# Fuel_Cell_Controller_V2.net
KiCad netlist of a schematic drawn in EAGLE
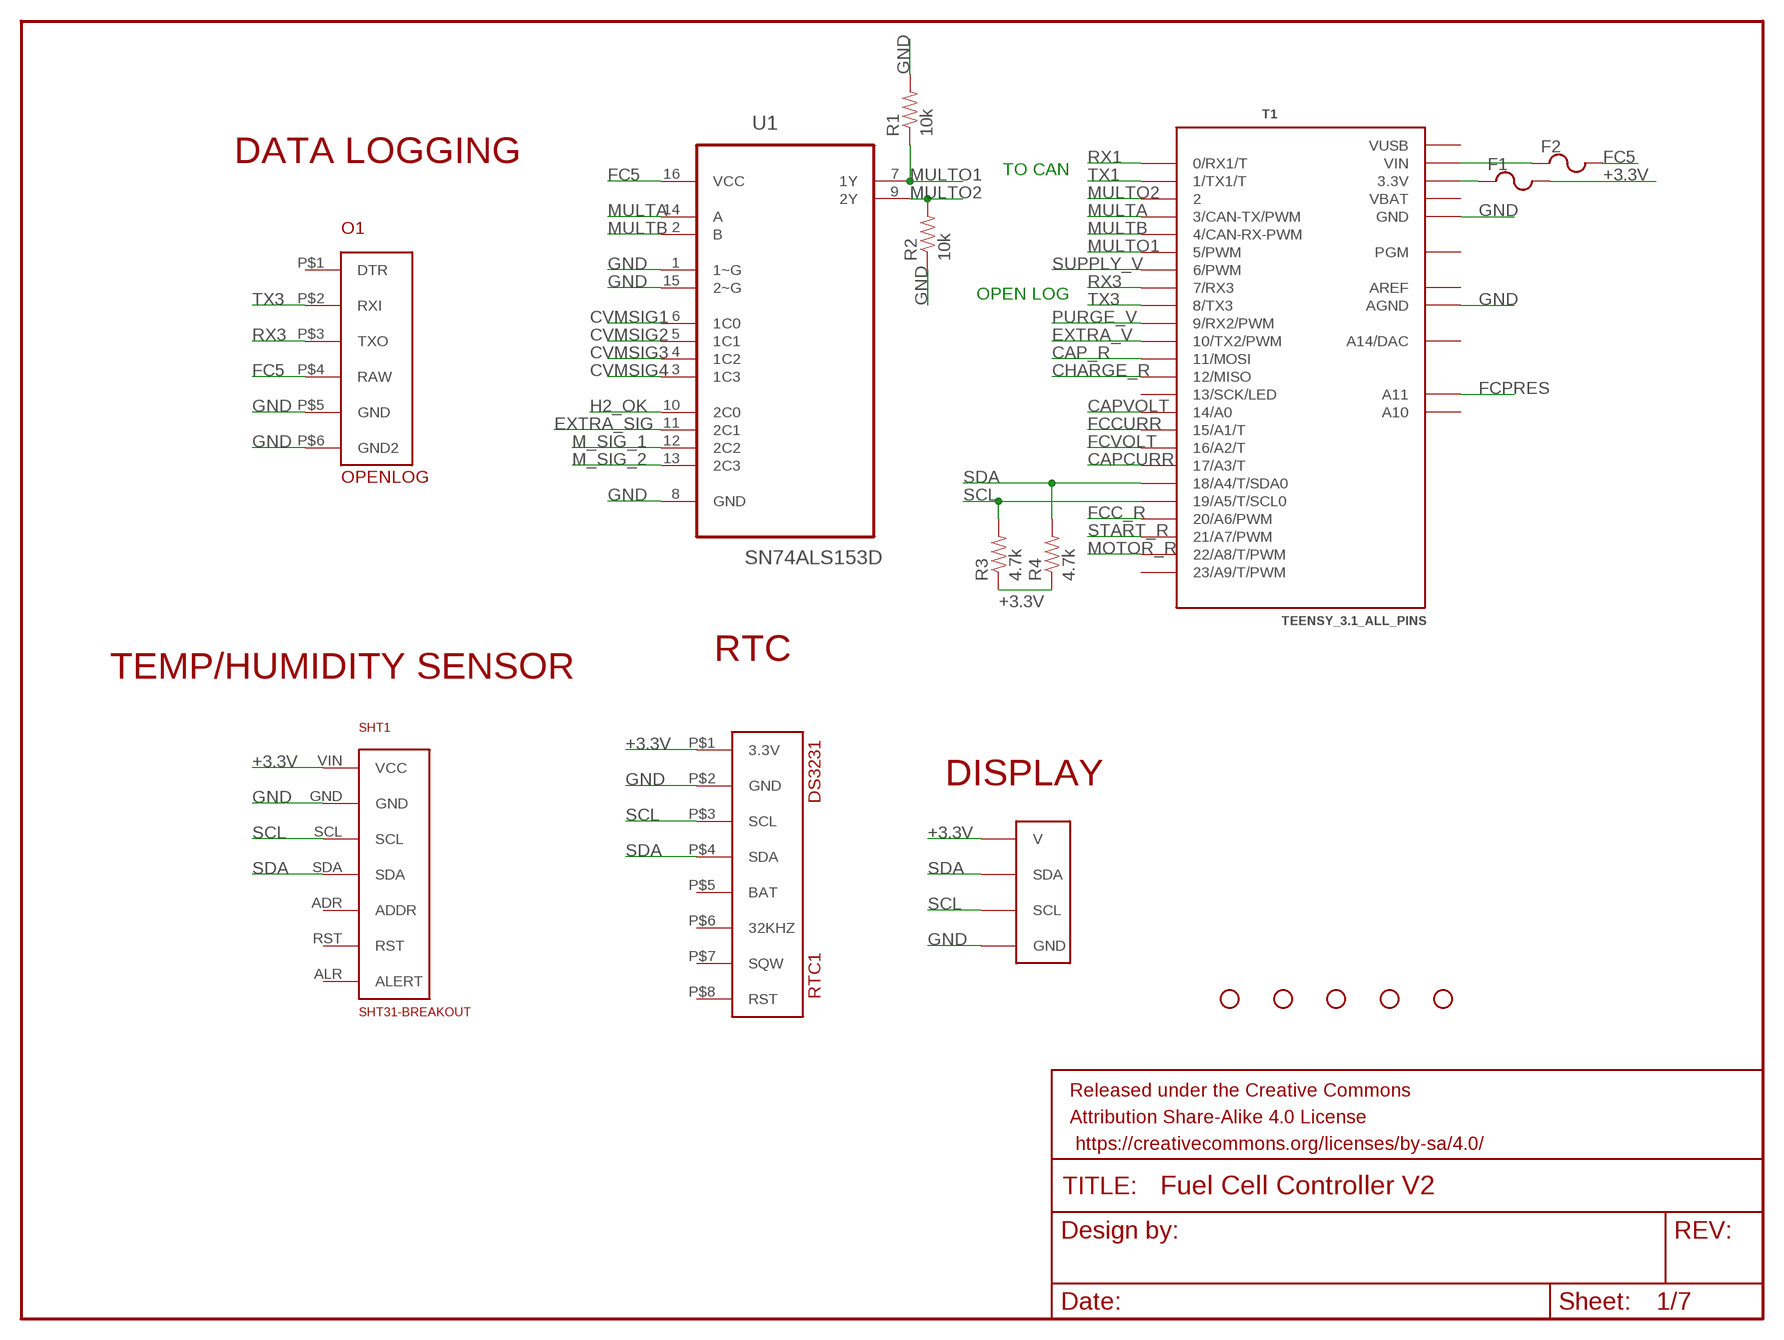
[diagram p0: schematic, sheet 1]
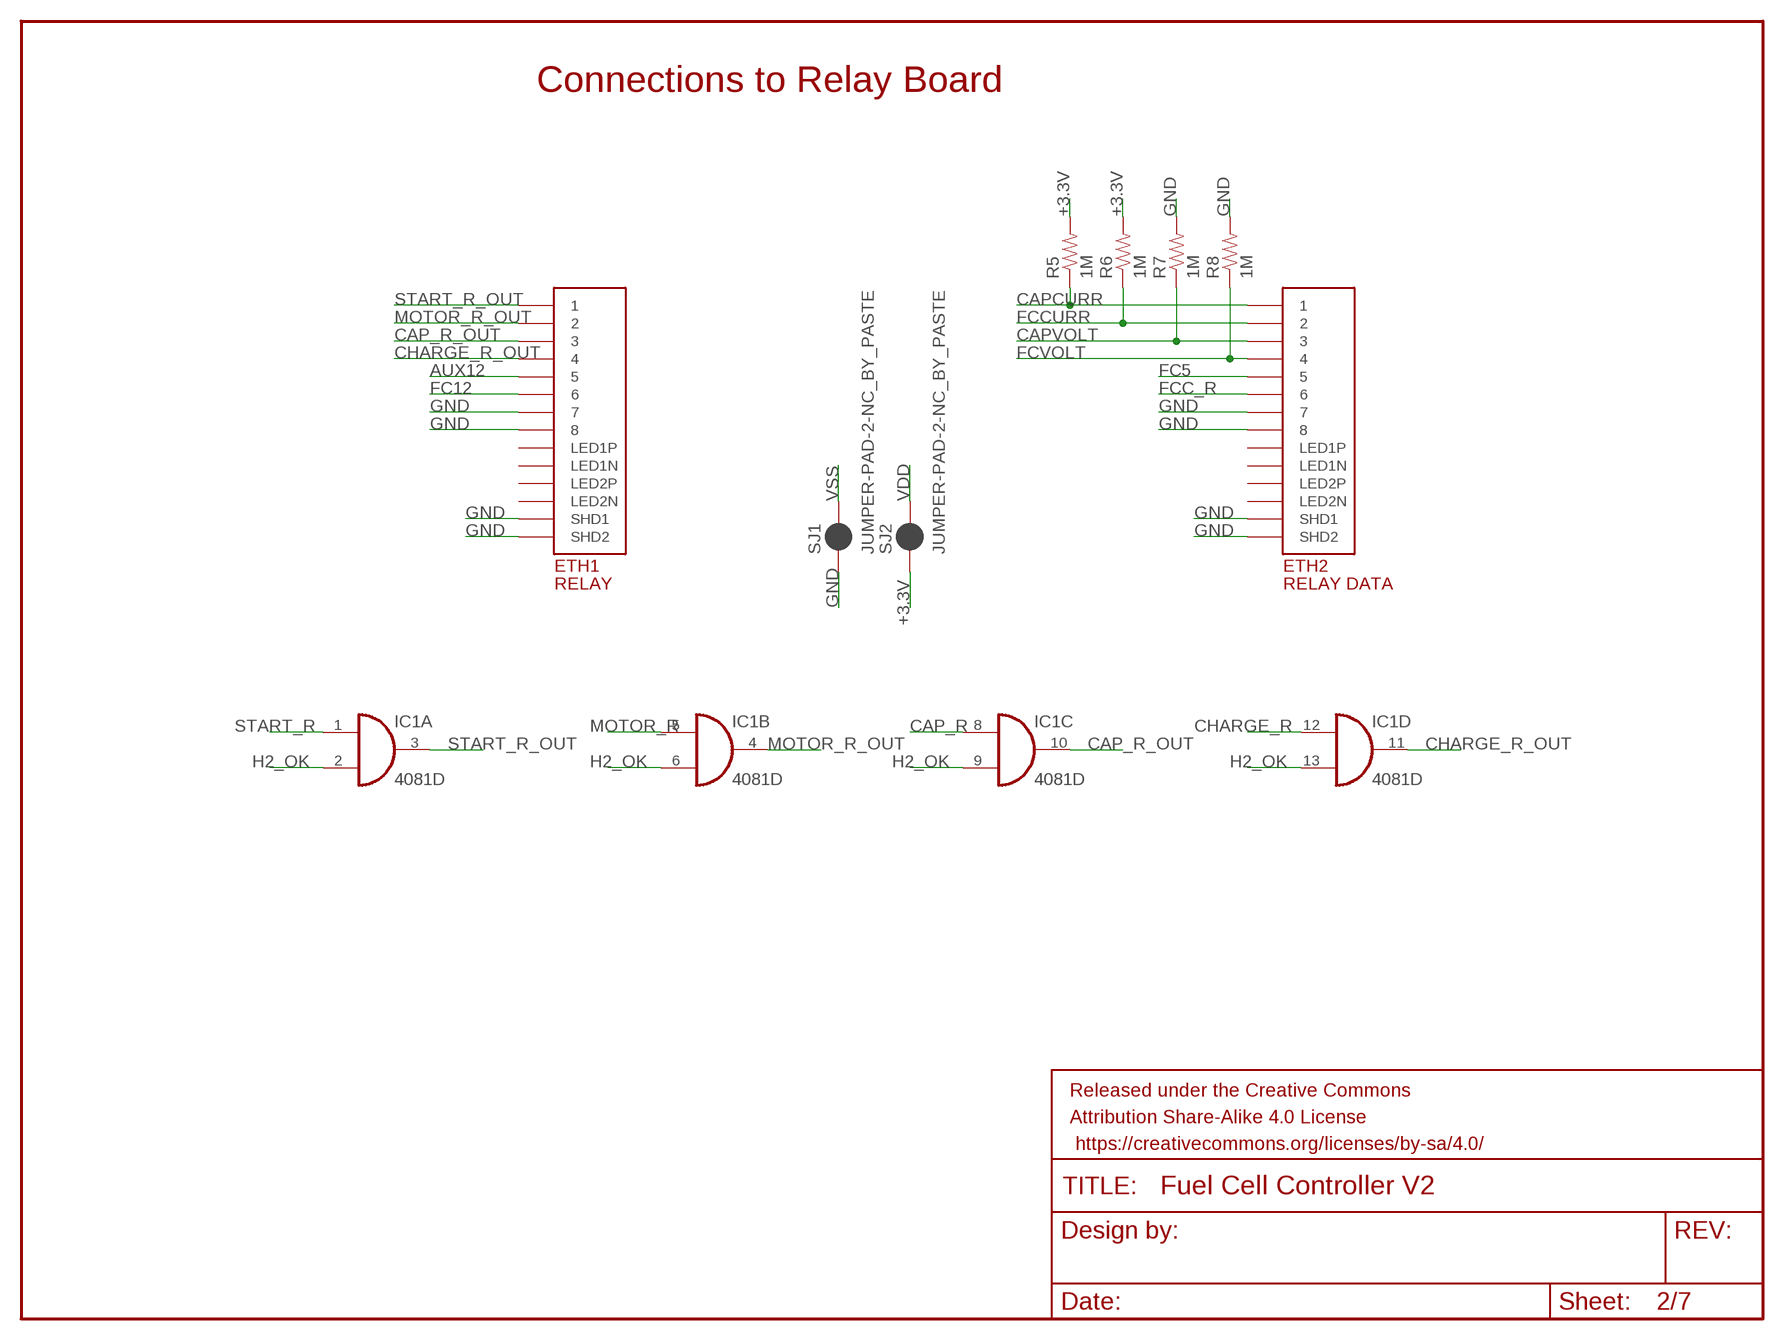
[diagram p1: schematic, sheet 2]
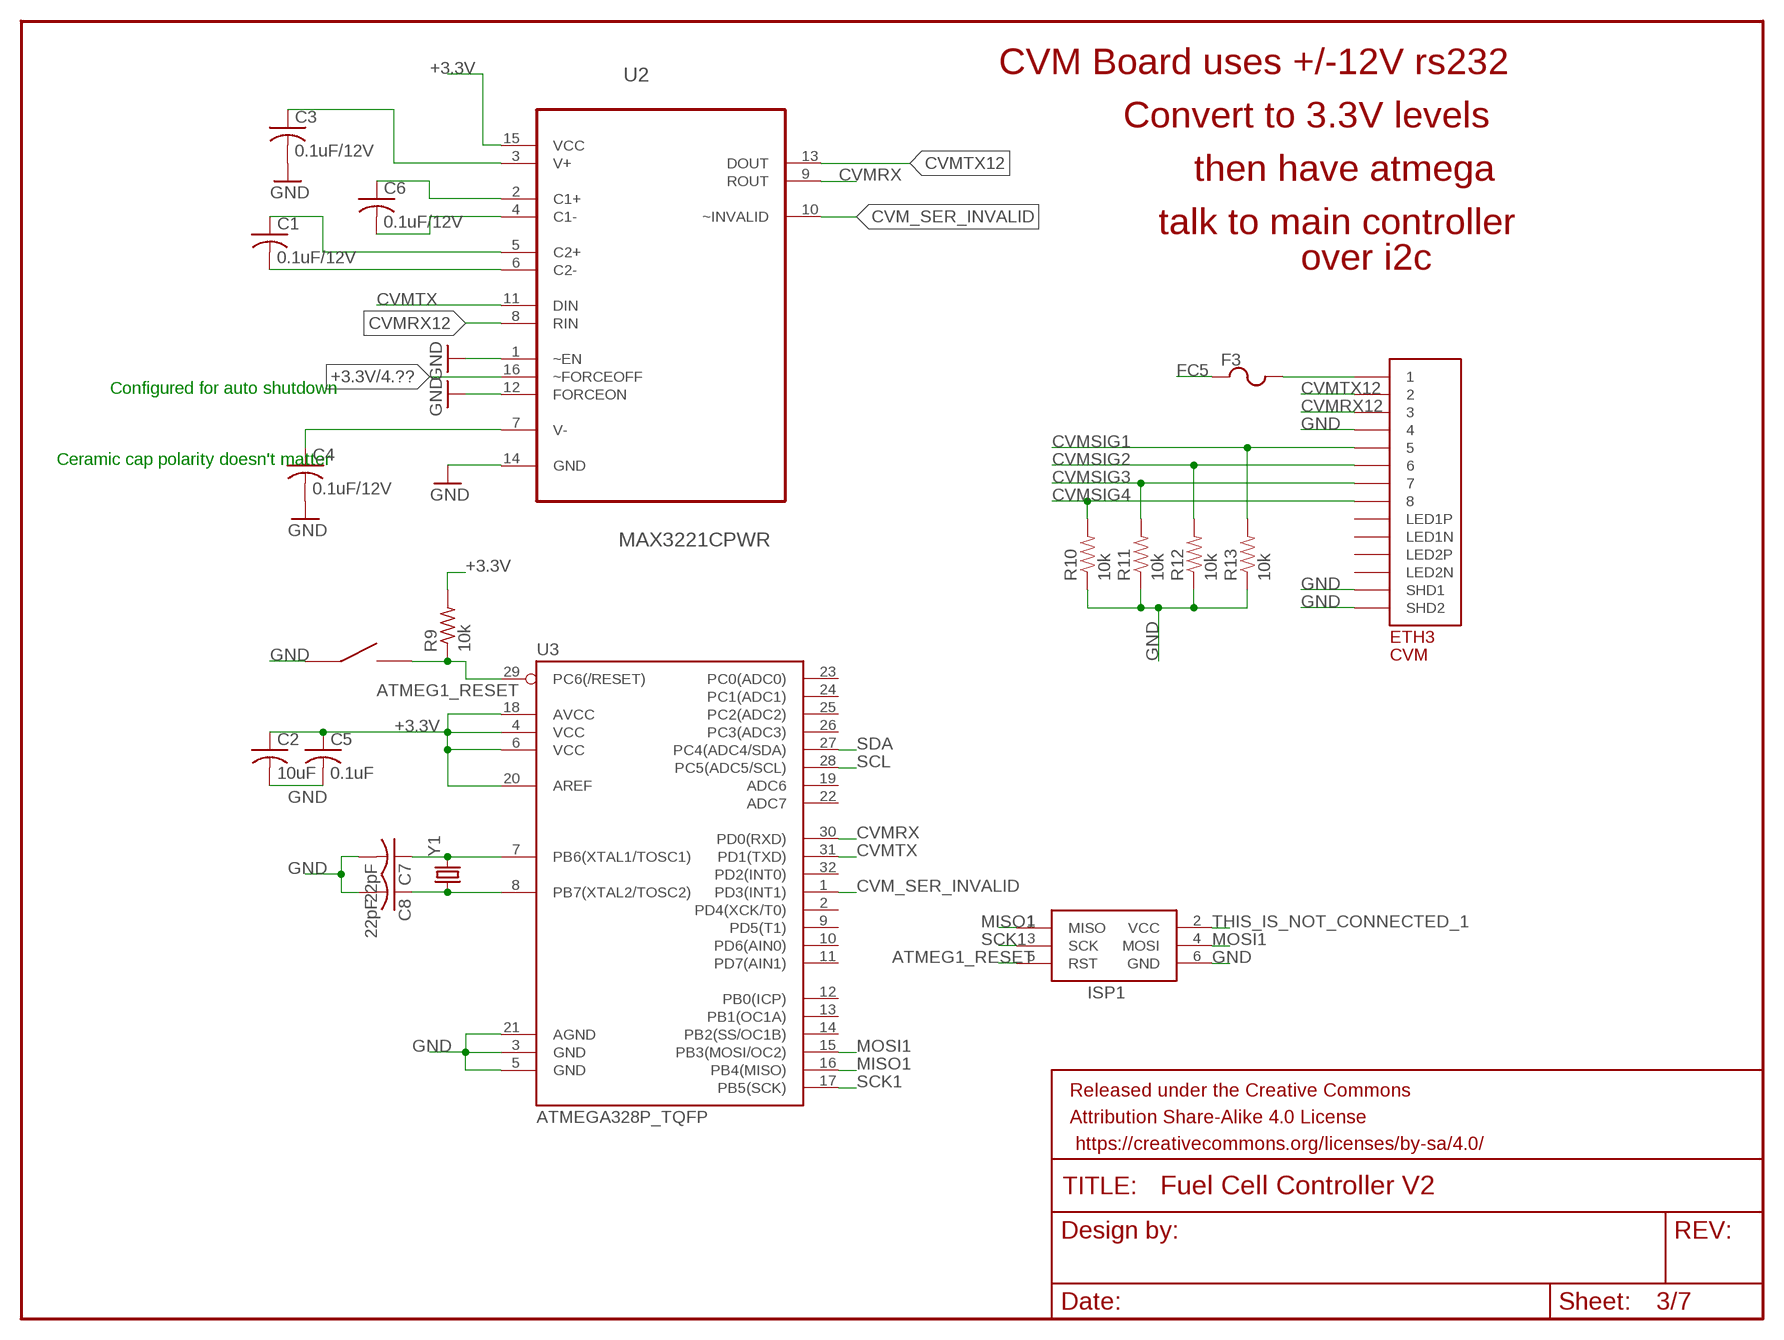
[diagram p2: schematic, sheet 3]
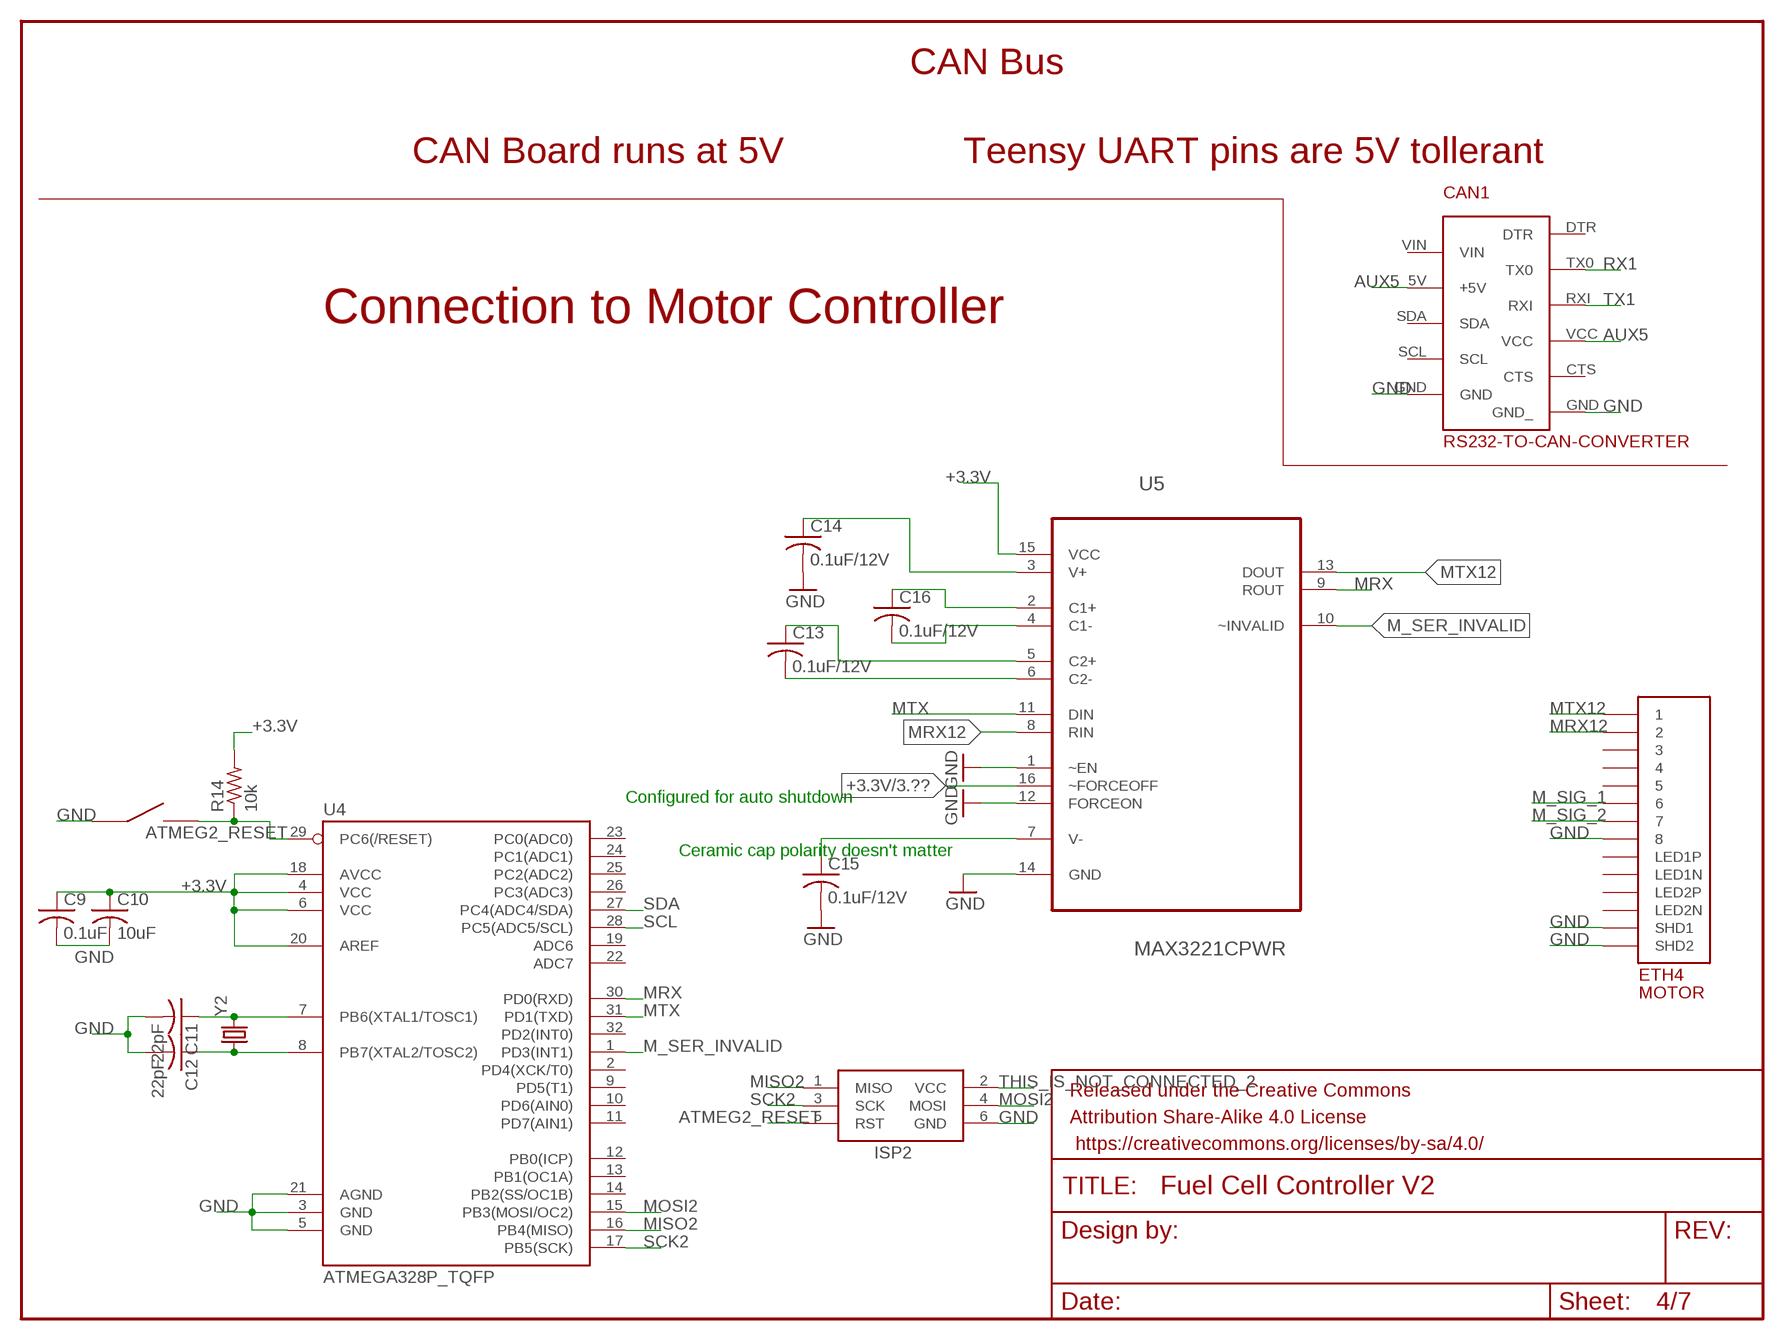
[diagram p3: schematic, sheet 4]
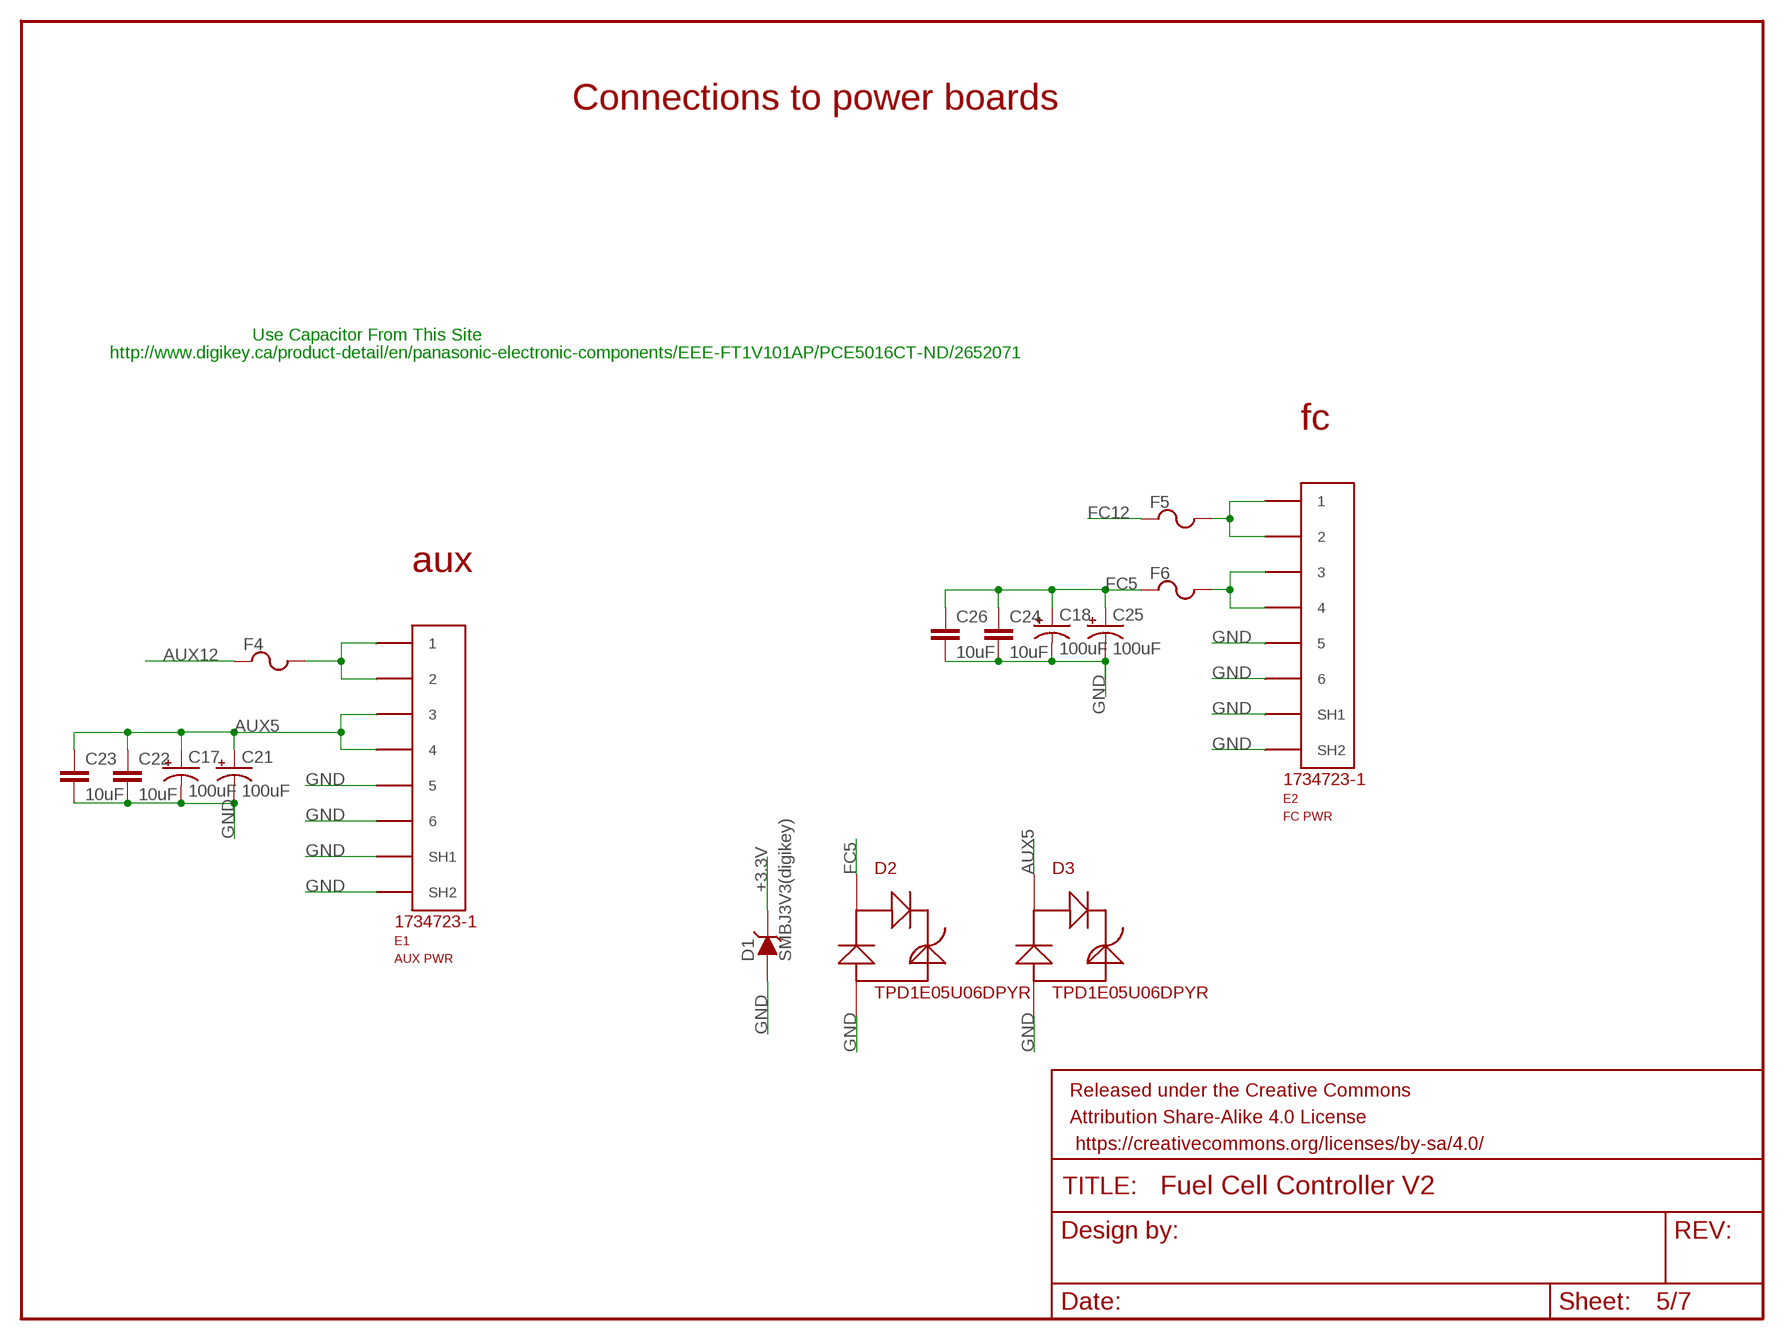
[diagram p4: schematic, sheet 5]
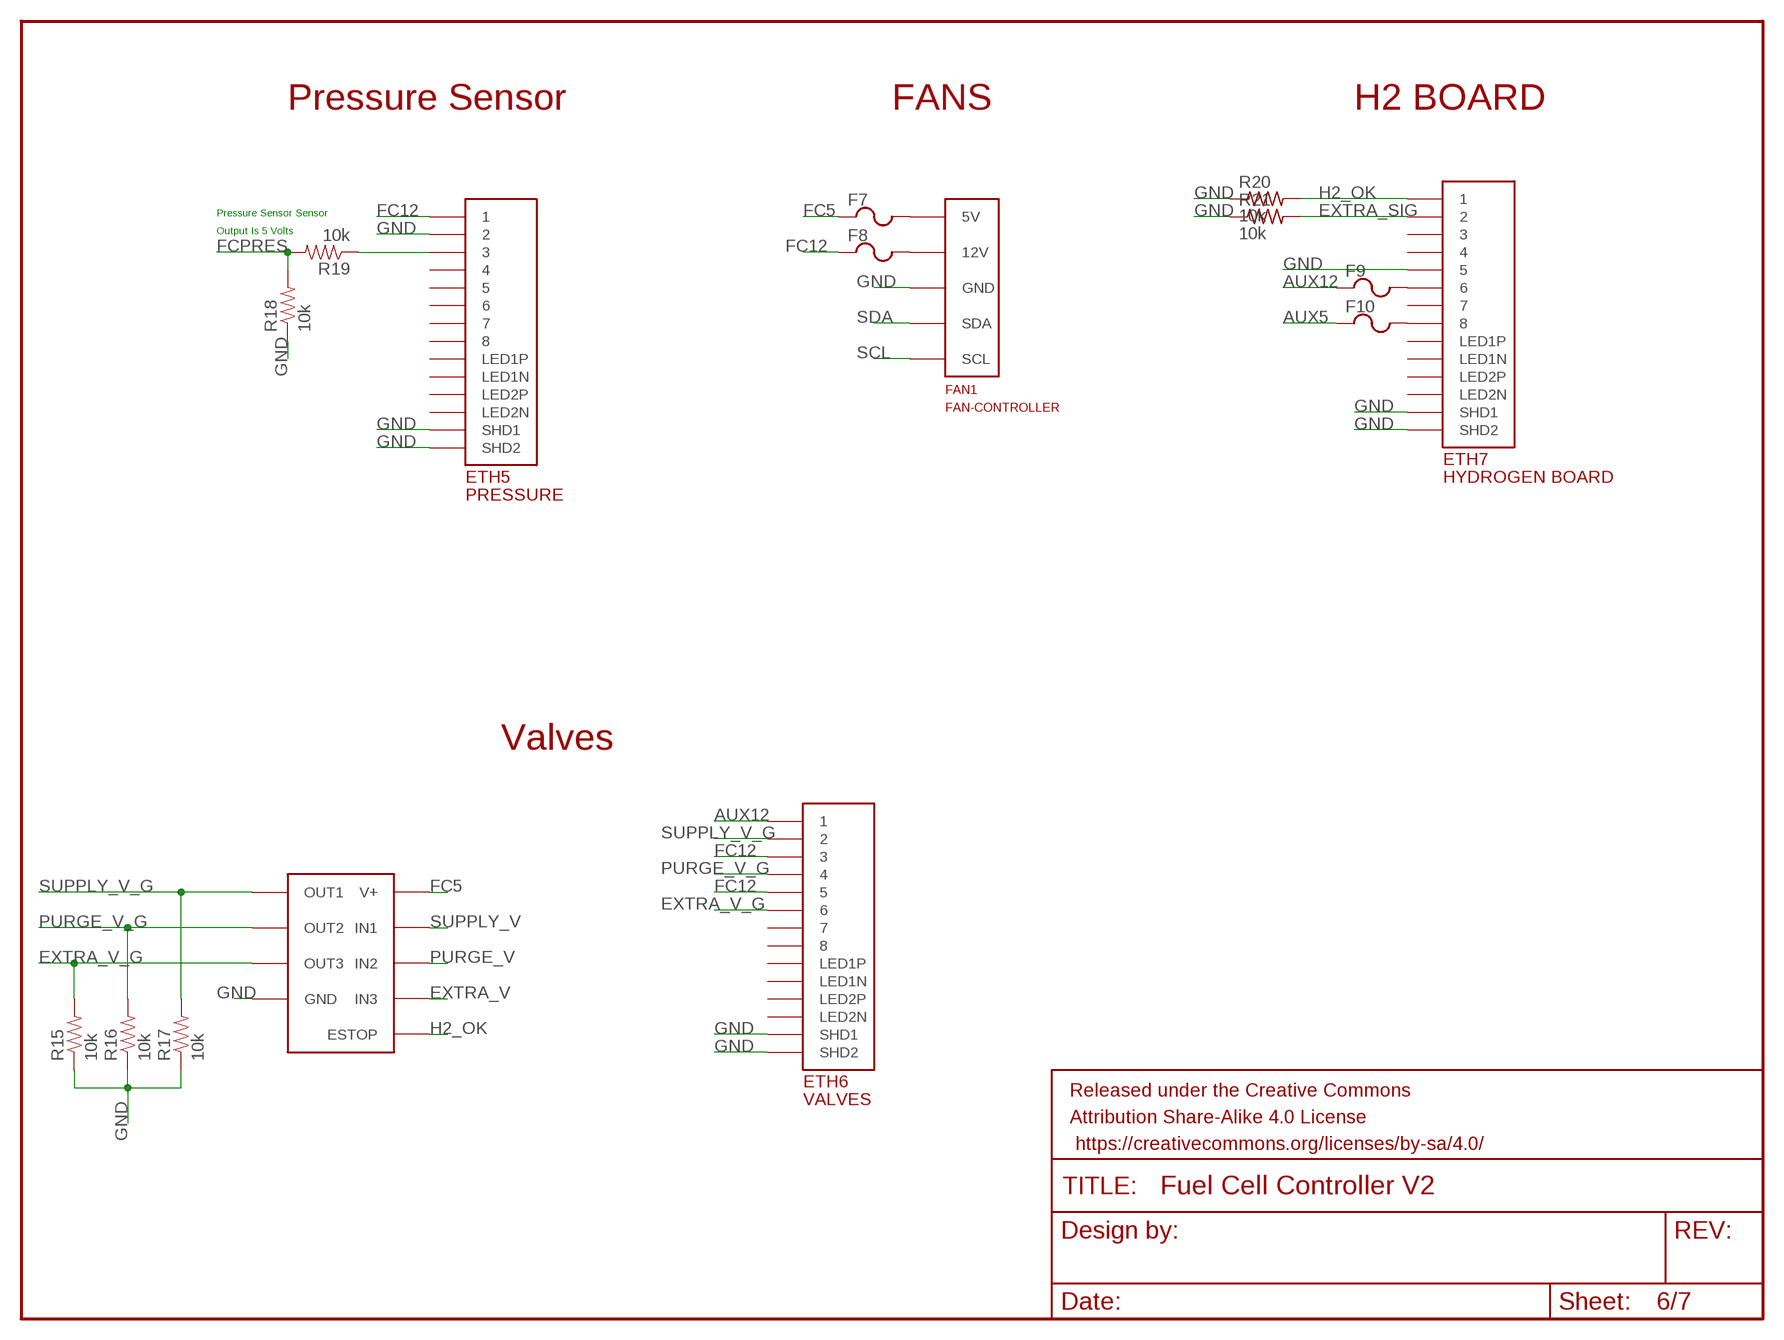
[diagram p5: schematic, sheet 6]
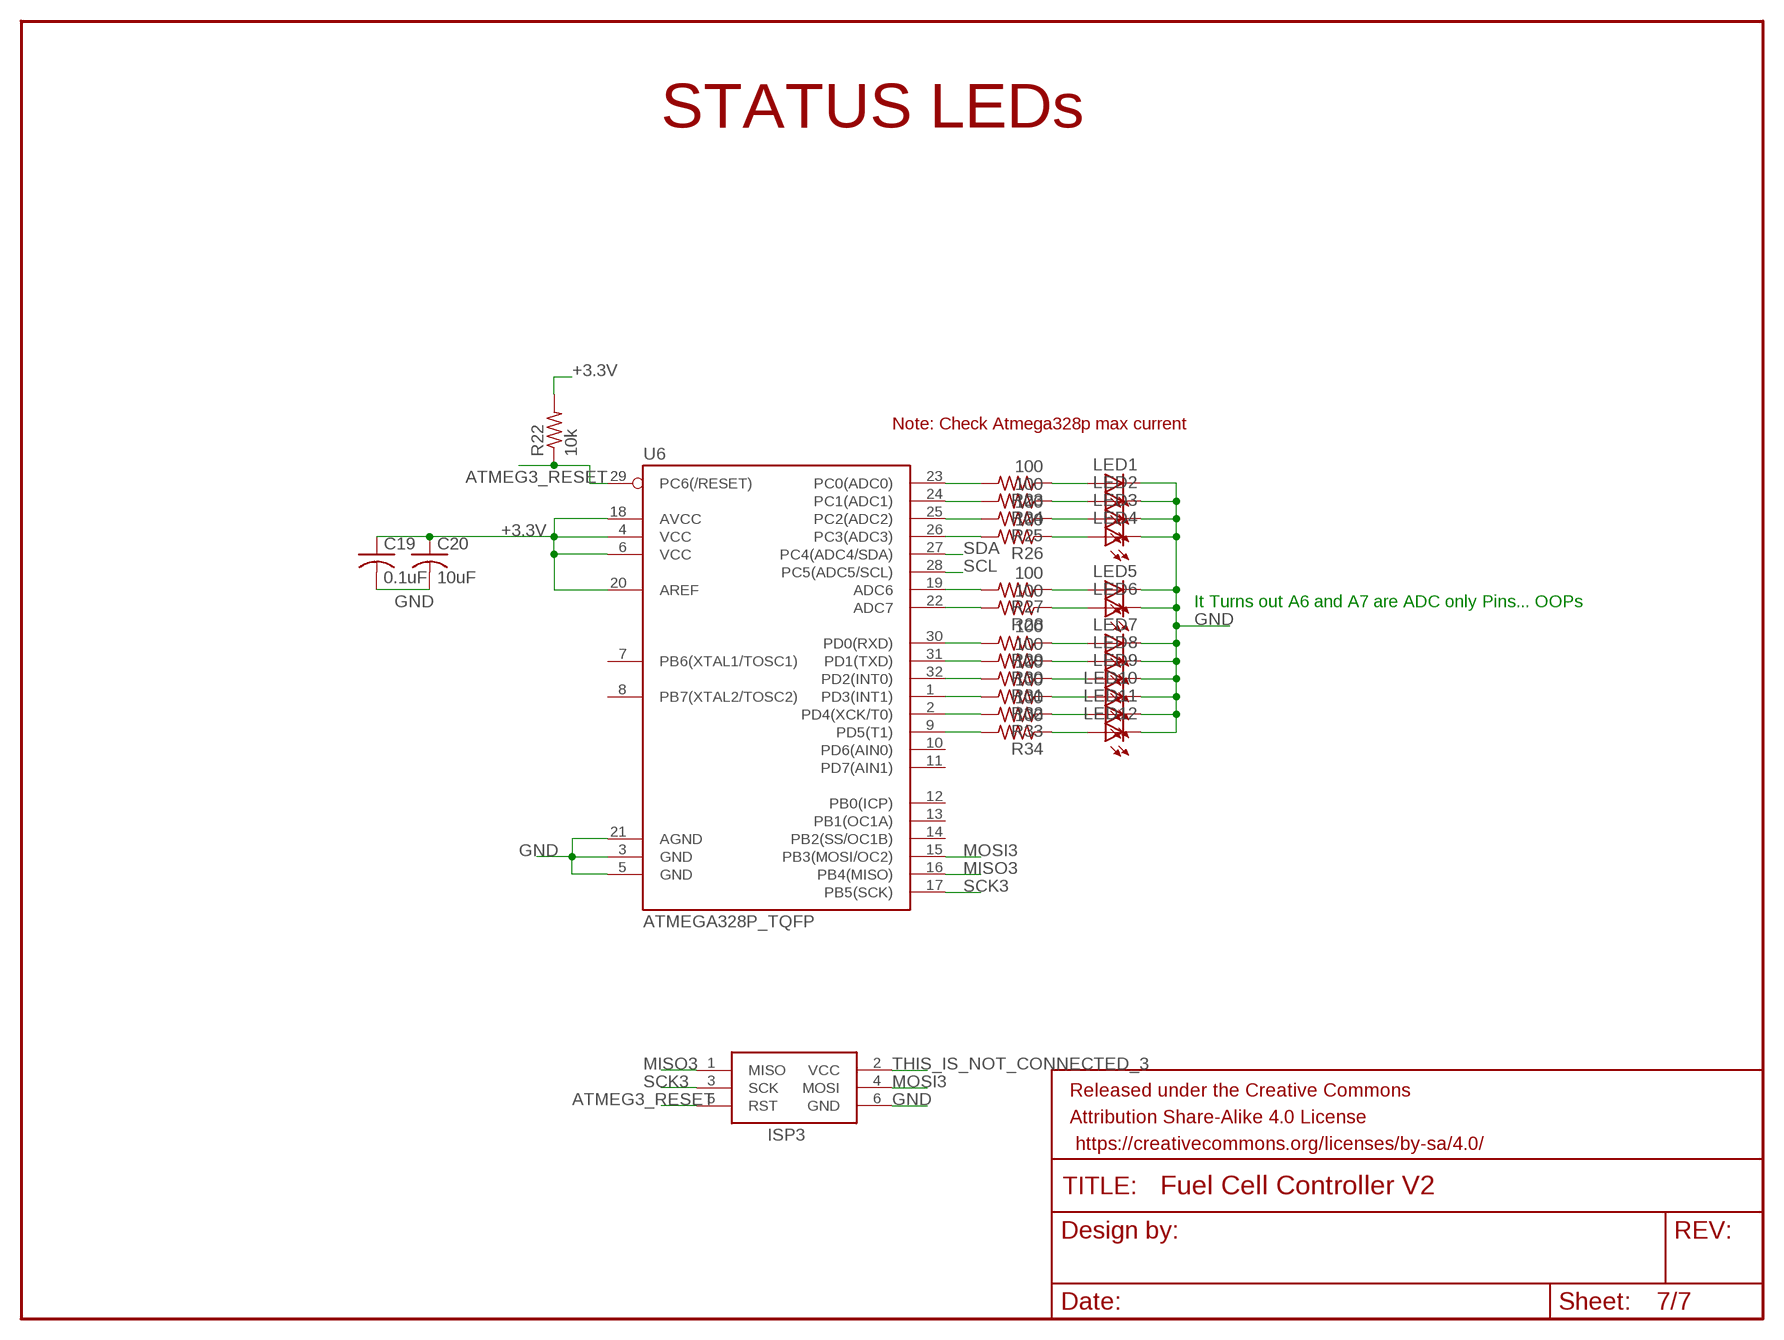
[diagram p6: schematic, sheet 7]

(export (version "E")
  (design (tool "Eeschema 10.0.6"))
  (components
    (comp (ref "ETH1")
      (value "RELAY")
      (footprint "eagle-import:A122645-ND")
      (libsource (lib "eagle-import") (part "ETHERNET"))
    )
    (comp (ref "ETH2")
      (value "RELAY DATA")
      (footprint "eagle-import:A122645-ND")
      (libsource (lib "eagle-import") (part "ETHERNET"))
    )
    (comp (ref "FRAME2")
      (value "FRAME-LETTERNO_PACKAGE")
      (footprint "eagle-import:DUMMY")
      (fields (field (name "DESIGNER") "Nobody"))
      (libsource (lib "eagle-import") (part "FRAME-LETTERNO_PACKAGE"))
    )
    (comp (ref "IC1")
      (value "4081D")
      (footprint "eagle-import:SO14")
      (libsource (lib "eagle-import") (part "4081D"))
    )
    (comp (ref "R5")
      (value "1M")
      (footprint "eagle-import:0805")
      (libsource (lib "eagle-import") (part "RESISTOR0805-RES"))
    )
    (comp (ref "R6")
      (value "1M")
      (footprint "eagle-import:0805")
      (libsource (lib "eagle-import") (part "RESISTOR0805-RES"))
    )
    (comp (ref "R7")
      (value "1M")
      (footprint "eagle-import:0805")
      (libsource (lib "eagle-import") (part "RESISTOR0805-RES"))
    )
    (comp (ref "R8")
      (value "1M")
      (footprint "eagle-import:0805")
      (libsource (lib "eagle-import") (part "RESISTOR0805-RES"))
    )
    (comp (ref "SJ1")
      (value "JUMPER-PAD-2-NC_BY_PASTE")
      (footprint "eagle-import:PAD-JUMPER-2-NC_BY_PASTE_YES_SILK")
      (libsource (lib "eagle-import") (part "JUMPER-PAD-2-NC_BY_PASTE"))
    )
    (comp (ref "SJ2")
      (value "JUMPER-PAD-2-NC_BY_PASTE")
      (footprint "eagle-import:PAD-JUMPER-2-NC_BY_PASTE_YES_SILK")
      (libsource (lib "eagle-import") (part "JUMPER-PAD-2-NC_BY_PASTE"))
    )
    (comp (ref "C19")
      (value "0.1uF")
      (footprint "eagle-import:C0603")
      (libsource (lib "eagle-import") (part "adafruit_C-USC0603"))
    )
    (comp (ref "C20")
      (value "10uF")
      (footprint "eagle-import:C0603")
      (libsource (lib "eagle-import") (part "adafruit_C-USC0603"))
    )
    (comp (ref "FRAME7")
      (value "FRAME-LETTERNO_PACKAGE")
      (footprint "eagle-import:DUMMY")
      (fields (field (name "DESIGNER") "Nobody"))
      (libsource (lib "eagle-import") (part "FRAME-LETTERNO_PACKAGE"))
    )
    (comp (ref "ISP3")
      (value "AVRISP-BOX")
      (footprint "eagle-import:AVRISP-BOX")
      (libsource (lib "eagle-import") (part "AVRISP-BOX"))
    )
    (comp (ref "LED1")
      (value "LEDCHIPLED_0805")
      (footprint "eagle-import:CHIPLED_0805")
      (libsource (lib "eagle-import") (part "LEDCHIPLED_0805"))
    )
    (comp (ref "LED2")
      (value "LEDCHIPLED_0805")
      (footprint "eagle-import:CHIPLED_0805")
      (libsource (lib "eagle-import") (part "LEDCHIPLED_0805"))
    )
    (comp (ref "LED3")
      (value "LEDCHIPLED_0805")
      (footprint "eagle-import:CHIPLED_0805")
      (libsource (lib "eagle-import") (part "LEDCHIPLED_0805"))
    )
    (comp (ref "LED4")
      (value "LEDCHIPLED_0805")
      (footprint "eagle-import:CHIPLED_0805")
      (libsource (lib "eagle-import") (part "LEDCHIPLED_0805"))
    )
    (comp (ref "LED5")
      (value "LEDCHIPLED_0805")
      (footprint "eagle-import:CHIPLED_0805")
      (libsource (lib "eagle-import") (part "LEDCHIPLED_0805"))
    )
    (comp (ref "LED6")
      (value "LEDCHIPLED_0805")
      (footprint "eagle-import:CHIPLED_0805")
      (libsource (lib "eagle-import") (part "LEDCHIPLED_0805"))
    )
    (comp (ref "LED7")
      (value "LEDCHIPLED_0805")
      (footprint "eagle-import:CHIPLED_0805")
      (libsource (lib "eagle-import") (part "LEDCHIPLED_0805"))
    )
    (comp (ref "LED8")
      (value "LEDCHIPLED_0805")
      (footprint "eagle-import:CHIPLED_0805")
      (libsource (lib "eagle-import") (part "LEDCHIPLED_0805"))
    )
    (comp (ref "LED9")
      (value "LEDCHIPLED_0805")
      (footprint "eagle-import:CHIPLED_0805")
      (libsource (lib "eagle-import") (part "LEDCHIPLED_0805"))
    )
    (comp (ref "LED10")
      (value "LEDCHIPLED_0805")
      (footprint "eagle-import:CHIPLED_0805")
      (libsource (lib "eagle-import") (part "LEDCHIPLED_0805"))
    )
    (comp (ref "LED11")
      (value "LEDCHIPLED_0805")
      (footprint "eagle-import:CHIPLED_0805")
      (libsource (lib "eagle-import") (part "LEDCHIPLED_0805"))
    )
    (comp (ref "LED12")
      (value "LEDCHIPLED_0805")
      (footprint "eagle-import:CHIPLED_0805")
      (libsource (lib "eagle-import") (part "LEDCHIPLED_0805"))
    )
    (comp (ref "R22")
      (value "10k")
      (footprint "eagle-import:R0603")
      (libsource (lib "eagle-import") (part "R-US_R0603"))
    )
    (comp (ref "R23")
      (value "100")
      (footprint "eagle-import:R0603")
      (libsource (lib "eagle-import") (part "R-US_R0603"))
    )
    (comp (ref "R24")
      (value "100")
      (footprint "eagle-import:R0603")
      (libsource (lib "eagle-import") (part "R-US_R0603"))
    )
    (comp (ref "R25")
      (value "100")
      (footprint "eagle-import:R0603")
      (libsource (lib "eagle-import") (part "R-US_R0603"))
    )
    (comp (ref "R26")
      (value "100")
      (footprint "eagle-import:R0603")
      (libsource (lib "eagle-import") (part "R-US_R0603"))
    )
    (comp (ref "R27")
      (value "100")
      (footprint "eagle-import:R0603")
      (libsource (lib "eagle-import") (part "R-US_R0603"))
    )
    (comp (ref "R28")
      (value "100")
      (footprint "eagle-import:R0603")
      (libsource (lib "eagle-import") (part "R-US_R0603"))
    )
    (comp (ref "R29")
      (value "100")
      (footprint "eagle-import:R0603")
      (libsource (lib "eagle-import") (part "R-US_R0603"))
    )
    (comp (ref "R30")
      (value "100")
      (footprint "eagle-import:R0603")
      (libsource (lib "eagle-import") (part "R-US_R0603"))
    )
    (comp (ref "R31")
      (value "100")
      (footprint "eagle-import:R0603")
      (libsource (lib "eagle-import") (part "R-US_R0603"))
    )
    (comp (ref "R32")
      (value "100")
      (footprint "eagle-import:R0603")
      (libsource (lib "eagle-import") (part "R-US_R0603"))
    )
    (comp (ref "R33")
      (value "100")
      (footprint "eagle-import:R0603")
      (libsource (lib "eagle-import") (part "R-US_R0603"))
    )
    (comp (ref "R34")
      (value "100")
      (footprint "eagle-import:R0603")
      (libsource (lib "eagle-import") (part "R-US_R0603"))
    )
    (comp (ref "U6")
      (value "ATMEGA328P_TQFP")
      (footprint "eagle-import:TQFP32-08")
      (libsource (lib "eagle-import") (part "ATMEGA328P_TQFP"))
    )
    (comp (ref "F1")
      (value "POLYFUSE")
      (footprint "eagle-import:1206")
      (libsource (lib "eagle-import") (part "POLYFUSE"))
    )
    (comp (ref "F2")
      (value "POLYFUSE")
      (footprint "eagle-import:1206")
      (libsource (lib "eagle-import") (part "POLYFUSE"))
    )
    (comp (ref "FRAME1")
      (value "FRAME-LETTERNO_PACKAGE")
      (footprint "eagle-import:DUMMY")
      (fields (field (name "DESIGNER") "Reegan McAllister"))
      (libsource (lib "eagle-import") (part "FRAME-LETTERNO_PACKAGE"))
    )
    (comp (ref "LCD1")
      (value "LCD-BOARD")
      (footprint "eagle-import:LCD-BOARD")
      (libsource (lib "eagle-import") (part "LCD-BOARD"))
    )
    (comp (ref "O1")
      (value "OPENLOG")
      (footprint "eagle-import:OPENLOG")
      (libsource (lib "eagle-import") (part "OPENLOG"))
    )
    (comp (ref "R1")
      (value "10k")
      (footprint "eagle-import:0805")
      (libsource (lib "eagle-import") (part "RESISTOR0805-RES"))
    )
    (comp (ref "R2")
      (value "10k")
      (footprint "eagle-import:0805")
      (libsource (lib "eagle-import") (part "RESISTOR0805-RES"))
    )
    (comp (ref "R3")
      (value "4.7k")
      (footprint "eagle-import:0805")
      (libsource (lib "eagle-import") (part "RESISTOR0805-RES"))
    )
    (comp (ref "R4")
      (value "4.7k")
      (footprint "eagle-import:0805")
      (libsource (lib "eagle-import") (part "RESISTOR0805-RES"))
    )
    (comp (ref "RTC1")
      (value "DS3231")
      (footprint "eagle-import:DS3231")
      (libsource (lib "eagle-import") (part "DS3231"))
    )
    (comp (ref "SHT1")
      (value "SHT31-BREAKOUT")
      (footprint "eagle-import:SHT31-BREAKOUT")
      (libsource (lib "eagle-import") (part "SHT31-BREAKOUT"))
    )
    (comp (ref "STANDOFF1")
      (value "STAND-OFF")
      (footprint "eagle-import:STAND-OFF")
      (libsource (lib "eagle-import") (part "STAND-OFF"))
    )
    (comp (ref "STANDOFF2")
      (value "STAND-OFF")
      (footprint "eagle-import:STAND-OFF")
      (libsource (lib "eagle-import") (part "STAND-OFF"))
    )
    (comp (ref "STANDOFF3")
      (value "STAND-OFF")
      (footprint "eagle-import:STAND-OFF")
      (libsource (lib "eagle-import") (part "STAND-OFF"))
    )
    (comp (ref "STANDOFF4")
      (value "STAND-OFF")
      (footprint "eagle-import:STAND-OFF")
      (libsource (lib "eagle-import") (part "STAND-OFF"))
    )
    (comp (ref "STANDOFF5")
      (value "STAND-OFF")
      (footprint "eagle-import:STAND-OFF")
      (libsource (lib "eagle-import") (part "STAND-OFF"))
    )
    (comp (ref "T1")
      (value "TEENSY_3.1_ALL_PINS")
      (footprint "eagle-import:TEENSY3-ALL_PINS")
      (libsource (lib "eagle-import") (part "TEENSY_3.1_ALL_PINS"))
    )
    (comp (ref "U1")
      (value "SN74ALS153D")
      (footprint "eagle-import:SOIC127P600X175-16N")
      (libsource (lib "eagle-import") (part "SN74ALS153D"))
    )
    (comp (ref "C1")
      (value "0.1uF/12V")
      (footprint "eagle-import:C0805")
      (libsource (lib "eagle-import") (part "C-USC0805"))
    )
    (comp (ref "C2")
      (value "10uF")
      (footprint "eagle-import:C0603")
      (libsource (lib "eagle-import") (part "adafruit_C-USC0603"))
    )
    (comp (ref "C3")
      (value "0.1uF/12V")
      (footprint "eagle-import:C0805")
      (libsource (lib "eagle-import") (part "C-USC0805"))
    )
    (comp (ref "C4")
      (value "0.1uF/12V")
      (footprint "eagle-import:C0805")
      (libsource (lib "eagle-import") (part "C-USC0805"))
    )
    (comp (ref "C5")
      (value "0.1uF")
      (footprint "eagle-import:C0603")
      (libsource (lib "eagle-import") (part "adafruit_C-USC0603"))
    )
    (comp (ref "C6")
      (value "0.1uF/12V")
      (footprint "eagle-import:C0805")
      (libsource (lib "eagle-import") (part "C-USC0805"))
    )
    (comp (ref "C7")
      (value "22pF")
      (footprint "eagle-import:C0603")
      (libsource (lib "eagle-import") (part "adafruit_C-USC0603"))
    )
    (comp (ref "C8")
      (value "22pF")
      (footprint "eagle-import:C0603")
      (libsource (lib "eagle-import") (part "adafruit_C-USC0603"))
    )
    (comp (ref "ETH3")
      (value "CVM")
      (footprint "eagle-import:A122645-ND")
      (libsource (lib "eagle-import") (part "ETHERNET"))
    )
    (comp (ref "F3")
      (value "POLYFUSE")
      (footprint "eagle-import:1206")
      (libsource (lib "eagle-import") (part "POLYFUSE"))
    )
    (comp (ref "FRAME3")
      (value "FRAME-LETTERNO_PACKAGE")
      (footprint "eagle-import:DUMMY")
      (fields (field (name "DESIGNER") "Nobody"))
      (libsource (lib "eagle-import") (part "FRAME-LETTERNO_PACKAGE"))
    )
    (comp (ref "ISP1")
      (value "AVRISP-BOX")
      (footprint "eagle-import:AVRISP-BOX")
      (libsource (lib "eagle-import") (part "AVRISP-BOX"))
    )
    (comp (ref "R9")
      (value "10k")
      (footprint "eagle-import:R0603")
      (libsource (lib "eagle-import") (part "R-US_R0603"))
    )
    (comp (ref "R10")
      (value "10k")
      (footprint "eagle-import:0805")
      (libsource (lib "eagle-import") (part "RESISTOR0805-RES"))
    )
    (comp (ref "R11")
      (value "10k")
      (footprint "eagle-import:0805")
      (libsource (lib "eagle-import") (part "RESISTOR0805-RES"))
    )
    (comp (ref "R12")
      (value "10k")
      (footprint "eagle-import:0805")
      (libsource (lib "eagle-import") (part "RESISTOR0805-RES"))
    )
    (comp (ref "R13")
      (value "10k")
      (footprint "eagle-import:0805")
      (libsource (lib "eagle-import") (part "RESISTOR0805-RES"))
    )
    (comp (ref "S1")
      (value "EG4621CT-ND")
      (footprint "eagle-import:EG4621CT-ND")
      (libsource (lib "eagle-import") (part "EG4621CT-ND"))
    )
    (comp (ref "U2")
      (value "MAX3221CPWR")
      (footprint "eagle-import:SOP65P640X120-16N")
      (libsource (lib "eagle-import") (part "MAX3221CPWR"))
    )
    (comp (ref "U3")
      (value "ATMEGA328P_TQFP")
      (footprint "eagle-import:TQFP32-08")
      (libsource (lib "eagle-import") (part "ATMEGA328P_TQFP"))
    )
    (comp (ref "Y1")
      (value "CRYSTALHC49US")
      (footprint "eagle-import:HC49US")
      (libsource (lib "eagle-import") (part "CRYSTALHC49US"))
    )
    (comp (ref "C17")
      (value "100uF")
      (footprint "eagle-import:PANASONIC_D")
      (libsource (lib "eagle-import") (part "CAP_POLD"))
    )
    (comp (ref "C18")
      (value "100uF")
      (footprint "eagle-import:PANASONIC_D")
      (libsource (lib "eagle-import") (part "CAP_POLD"))
    )
    (comp (ref "C21")
      (value "100uF")
      (footprint "eagle-import:PANASONIC_D")
      (libsource (lib "eagle-import") (part "CAP_POLD"))
    )
    (comp (ref "C22")
      (value "10uF")
      (footprint "eagle-import:0805")
      (libsource (lib "eagle-import") (part "CAP0805"))
    )
    (comp (ref "C23")
      (value "10uF")
      (footprint "eagle-import:0805")
      (libsource (lib "eagle-import") (part "CAP0805"))
    )
    (comp (ref "C24")
      (value "10uF")
      (footprint "eagle-import:0805")
      (libsource (lib "eagle-import") (part "CAP0805"))
    )
    (comp (ref "C25")
      (value "100uF")
      (footprint "eagle-import:PANASONIC_D")
      (libsource (lib "eagle-import") (part "CAP_POLD"))
    )
    (comp (ref "C26")
      (value "10uF")
      (footprint "eagle-import:0805")
      (libsource (lib "eagle-import") (part "CAP0805"))
    )
    (comp (ref "D1")
      (value "SMBJ3V3(digikey)")
      (footprint "eagle-import:DO-214AB")
      (libsource (lib "eagle-import") (part "5KASMC"))
    )
    (comp (ref "D2")
      (value "TPD1E05U06DPYR")
      (footprint "eagle-import:2-XDFN")
      (libsource (lib "eagle-import") (part "TPD1E05U06DPYR"))
    )
    (comp (ref "D3")
      (value "TPD1E05U06DPYR")
      (footprint "eagle-import:2-XDFN")
      (libsource (lib "eagle-import") (part "TPD1E05U06DPYR"))
    )
    (comp (ref "E1")
      (value "AUX PWR")
      (footprint "eagle-import:1734723-1_RJ11")
      (libsource (lib "eagle-import") (part "5555140-6"))
    )
    (comp (ref "E2")
      (value "FC PWR")
      (footprint "eagle-import:1734723-1_RJ11")
      (libsource (lib "eagle-import") (part "5555140-6"))
    )
    (comp (ref "F4")
      (value "POLYFUSE")
      (footprint "eagle-import:1206")
      (libsource (lib "eagle-import") (part "POLYFUSE"))
    )
    (comp (ref "F5")
      (value "POLYFUSE")
      (footprint "eagle-import:1206")
      (libsource (lib "eagle-import") (part "POLYFUSE"))
    )
    (comp (ref "F6")
      (value "POLYFUSE")
      (footprint "eagle-import:1206")
      (libsource (lib "eagle-import") (part "POLYFUSE"))
    )
    (comp (ref "FRAME5")
      (value "FRAME-LETTERNO_PACKAGE")
      (footprint "eagle-import:DUMMY")
      (fields (field (name "DESIGNER") "Nobody"))
      (libsource (lib "eagle-import") (part "FRAME-LETTERNO_PACKAGE"))
    )
    (comp (ref "ETH5")
      (value "PRESSURE")
      (footprint "eagle-import:A122645-ND")
      (libsource (lib "eagle-import") (part "ETHERNET"))
    )
    (comp (ref "ETH6")
      (value "VALVES")
      (footprint "eagle-import:A122645-ND")
      (libsource (lib "eagle-import") (part "ETHERNET"))
    )
    (comp (ref "ETH7")
      (value "HYDROGEN BOARD")
      (footprint "eagle-import:A122645-ND")
      (libsource (lib "eagle-import") (part "ETHERNET"))
    )
    (comp (ref "F7")
      (value "POLYFUSE")
      (footprint "eagle-import:1206")
      (libsource (lib "eagle-import") (part "POLYFUSE"))
    )
    (comp (ref "F8")
      (value "POLYFUSE")
      (footprint "eagle-import:1206")
      (libsource (lib "eagle-import") (part "POLYFUSE"))
    )
    (comp (ref "F9")
      (value "POLYFUSE")
      (footprint "eagle-import:1206")
      (libsource (lib "eagle-import") (part "POLYFUSE"))
    )
    (comp (ref "F10")
      (value "POLYFUSE")
      (footprint "eagle-import:1206")
      (libsource (lib "eagle-import") (part "POLYFUSE"))
    )
    (comp (ref "FAN1")
      (value "FAN-CONTROLLER")
      (footprint "eagle-import:FAN-CONTROLLER")
      (libsource (lib "eagle-import") (part "FAN-CONTROLLER"))
    )
    (comp (ref "FRAME6")
      (value "FRAME-LETTERNO_PACKAGE")
      (footprint "eagle-import:DUMMY")
      (fields (field (name "DESIGNER") "Nobody"))
      (libsource (lib "eagle-import") (part "FRAME-LETTERNO_PACKAGE"))
    )
    (comp (ref "M1")
      (value "MOSFETBOARD")
      (footprint "eagle-import:MOSFET-BOARD")
      (libsource (lib "eagle-import") (part "MOSFETBOARD"))
    )
    (comp (ref "R15")
      (value "10k")
      (footprint "eagle-import:0805")
      (libsource (lib "eagle-import") (part "RESISTOR0805-RES"))
    )
    (comp (ref "R16")
      (value "10k")
      (footprint "eagle-import:0805")
      (libsource (lib "eagle-import") (part "RESISTOR0805-RES"))
    )
    (comp (ref "R17")
      (value "10k")
      (footprint "eagle-import:0805")
      (libsource (lib "eagle-import") (part "RESISTOR0805-RES"))
    )
    (comp (ref "R18")
      (value "10k")
      (footprint "eagle-import:0805")
      (libsource (lib "eagle-import") (part "RESISTOR0805-RES"))
    )
    (comp (ref "R19")
      (value "10k")
      (footprint "eagle-import:0805")
      (libsource (lib "eagle-import") (part "RESISTOR0805-RES"))
    )
    (comp (ref "R20")
      (value "10k")
      (footprint "eagle-import:R0603")
      (libsource (lib "eagle-import") (part "R-US_R0603"))
    )
    (comp (ref "R21")
      (value "10k")
      (footprint "eagle-import:R0603")
      (libsource (lib "eagle-import") (part "R-US_R0603"))
    )
    (comp (ref "C9")
      (value "0.1uF")
      (footprint "eagle-import:C0603")
      (libsource (lib "eagle-import") (part "adafruit_C-USC0603"))
    )
    (comp (ref "C10")
      (value "10uF")
      (footprint "eagle-import:C0603")
      (libsource (lib "eagle-import") (part "adafruit_C-USC0603"))
    )
    (comp (ref "C11")
      (value "22pF")
      (footprint "eagle-import:C0603")
      (libsource (lib "eagle-import") (part "adafruit_C-USC0603"))
    )
    (comp (ref "C12")
      (value "22pF")
      (footprint "eagle-import:C0603")
      (libsource (lib "eagle-import") (part "adafruit_C-USC0603"))
    )
    (comp (ref "C13")
      (value "0.1uF/12V")
      (footprint "eagle-import:C0805")
      (libsource (lib "eagle-import") (part "C-USC0805"))
    )
    (comp (ref "C14")
      (value "0.1uF/12V")
      (footprint "eagle-import:C0805")
      (libsource (lib "eagle-import") (part "C-USC0805"))
    )
    (comp (ref "C15")
      (value "0.1uF/12V")
      (footprint "eagle-import:C0805")
      (libsource (lib "eagle-import") (part "C-USC0805"))
    )
    (comp (ref "C16")
      (value "0.1uF/12V")
      (footprint "eagle-import:C0805")
      (libsource (lib "eagle-import") (part "C-USC0805"))
    )
    (comp (ref "CAN1")
      (value "RS232-TO-CAN-CONVERTER")
      (footprint "eagle-import:RS232-TO-CAN-CONVERTER")
      (libsource (lib "eagle-import") (part "RS232-TO-CAN-CONVERTER"))
    )
    (comp (ref "ETH4")
      (value "MOTOR")
      (footprint "eagle-import:A122645-ND")
      (libsource (lib "eagle-import") (part "ETHERNET"))
    )
    (comp (ref "FRAME4")
      (value "FRAME-LETTERNO_PACKAGE")
      (footprint "eagle-import:DUMMY")
      (fields (field (name "DESIGNER") "Nobody"))
      (libsource (lib "eagle-import") (part "FRAME-LETTERNO_PACKAGE"))
    )
    (comp (ref "ISP2")
      (value "AVRISP-BOX")
      (footprint "eagle-import:AVRISP-BOX")
      (libsource (lib "eagle-import") (part "AVRISP-BOX"))
    )
    (comp (ref "R14")
      (value "10k")
      (footprint "eagle-import:R0603")
      (libsource (lib "eagle-import") (part "R-US_R0603"))
    )
    (comp (ref "S2")
      (value "EG4621CT-ND")
      (footprint "eagle-import:EG4621CT-ND")
      (libsource (lib "eagle-import") (part "EG4621CT-ND"))
    )
    (comp (ref "U4")
      (value "ATMEGA328P_TQFP")
      (footprint "eagle-import:TQFP32-08")
      (libsource (lib "eagle-import") (part "ATMEGA328P_TQFP"))
    )
    (comp (ref "U5")
      (value "MAX3221CPWR")
      (footprint "eagle-import:SOP65P640X120-16N")
      (libsource (lib "eagle-import") (part "MAX3221CPWR"))
    )
    (comp (ref "Y2")
      (value "CRYSTALHC49US")
      (footprint "eagle-import:HC49US")
      (libsource (lib "eagle-import") (part "CRYSTALHC49US"))
    )
  )
  (nets
    (net (code "1") (name "+3.3V") (class "Default")
      (node (ref "C10") (pin "1") (pinfunction "1_1") (pintype "passive"))
      (node (ref "C19") (pin "1") (pinfunction "1_1") (pintype "passive"))
      (node (ref "C2") (pin "1") (pinfunction "1_1") (pintype "passive"))
      (node (ref "C20") (pin "1") (pinfunction "1_1") (pintype "passive"))
      (node (ref "C5") (pin "1") (pinfunction "1_1") (pintype "passive"))
      (node (ref "C9") (pin "1") (pinfunction "1_1") (pintype "passive"))
      (node (ref "D1") (pin "C") (pinfunction "C_C") (pintype "passive"))
      (node (ref "F1") (pin "2") (pinfunction "2_2") (pintype "passive"))
      (node (ref "LCD1") (pin "V") (pinfunction "V_V") (pintype "bidirectional"))
      (node (ref "R14") (pin "2") (pinfunction "2_2") (pintype "passive"))
      (node (ref "R22") (pin "2") (pinfunction "2_2") (pintype "passive"))
      (node (ref "R3") (pin "1") (pinfunction "1_1") (pintype "passive"))
      (node (ref "R4") (pin "1") (pinfunction "1_1") (pintype "passive"))
      (node (ref "R5") (pin "2") (pinfunction "2_2") (pintype "passive"))
      (node (ref "R6") (pin "2") (pinfunction "2_2") (pintype "passive"))
      (node (ref "R9") (pin "2") (pinfunction "2_2") (pintype "passive"))
      (node (ref "RTC1") (pin "P$1") (pinfunction "3.3V_P$1") (pintype "bidirectional"))
      (node (ref "SHT1") (pin "VIN") (pinfunction "VCC_VIN") (pintype "bidirectional"))
      (node (ref "SJ2") (pin "1") (pinfunction "1_1") (pintype "passive"))
      (node (ref "U2") (pin "15") (pinfunction "VCC_15") (pintype "power_in"))
      (node (ref "U2") (pin "16") (pinfunction "~{FORCEOFF}_16") (pintype "input"))
      (node (ref "U3") (pin "18") (pinfunction "AVCC_18") (pintype "bidirectional"))
      (node (ref "U3") (pin "20") (pinfunction "AREF_20") (pintype "bidirectional"))
      (node (ref "U3") (pin "4") (pinfunction "VCC_4") (pintype "bidirectional"))
      (node (ref "U3") (pin "6") (pinfunction "VCC_6") (pintype "bidirectional"))
      (node (ref "U4") (pin "18") (pinfunction "AVCC_18") (pintype "bidirectional"))
      (node (ref "U4") (pin "20") (pinfunction "AREF_20") (pintype "bidirectional"))
      (node (ref "U4") (pin "4") (pinfunction "VCC_4") (pintype "bidirectional"))
      (node (ref "U4") (pin "6") (pinfunction "VCC_6") (pintype "bidirectional"))
      (node (ref "U5") (pin "15") (pinfunction "VCC_15") (pintype "power_in"))
      (node (ref "U5") (pin "16") (pinfunction "~{FORCEOFF}_16") (pintype "input"))
      (node (ref "U6") (pin "18") (pinfunction "AVCC_18") (pintype "bidirectional"))
      (node (ref "U6") (pin "20") (pinfunction "AREF_20") (pintype "bidirectional"))
      (node (ref "U6") (pin "4") (pinfunction "VCC_4") (pintype "bidirectional"))
      (node (ref "U6") (pin "6") (pinfunction "VCC_6") (pintype "bidirectional"))
    )
    (net (code "2") (name "AREF") (class "Default")
      (node (ref "T1") (pin "AREF") (pinfunction "AREF_AREF") (pintype "power_in"))
    )
    (net (code "3") (name "ATMEG1_RESET") (class "Default")
      (node (ref "ISP1") (pin "5") (pinfunction "RST_5") (pintype "output"))
      (node (ref "R9") (pin "1") (pinfunction "1_1") (pintype "passive"))
      (node (ref "S1") (pin "P$3") (pinfunction "P$2_P$3") (pintype "bidirectional"))
      (node (ref "S1") (pin "P$4") (pinfunction "P$2_P$4") (pintype "bidirectional"))
      (node (ref "U3") (pin "29") (pinfunction "PC6(/RESET)_29") (pintype "bidirectional"))
    )
    (net (code "4") (name "ATMEG2_RESET") (class "Default")
      (node (ref "ISP2") (pin "5") (pinfunction "RST_5") (pintype "output"))
      (node (ref "R14") (pin "1") (pinfunction "1_1") (pintype "passive"))
      (node (ref "S2") (pin "P$3") (pinfunction "P$2_P$3") (pintype "bidirectional"))
      (node (ref "S2") (pin "P$4") (pinfunction "P$2_P$4") (pintype "bidirectional"))
      (node (ref "U4") (pin "29") (pinfunction "PC6(/RESET)_29") (pintype "bidirectional"))
    )
    (net (code "5") (name "ATMEG3_RESET") (class "Default")
      (node (ref "ISP3") (pin "5") (pinfunction "RST_5") (pintype "output"))
      (node (ref "R22") (pin "1") (pinfunction "1_1") (pintype "passive"))
      (node (ref "U6") (pin "29") (pinfunction "PC6(/RESET)_29") (pintype "bidirectional"))
    )
    (net (code "6") (name "AUX5") (class "Default")
      (node (ref "C17") (pin "+") (pinfunction "+_+") (pintype "passive"))
      (node (ref "C21") (pin "+") (pinfunction "+_+") (pintype "passive"))
      (node (ref "C22") (pin "1") (pinfunction "1_1") (pintype "passive"))
      (node (ref "C23") (pin "1") (pinfunction "1_1") (pintype "passive"))
      (node (ref "CAN1") (pin "5V") (pinfunction "+5V_5V") (pintype "bidirectional"))
      (node (ref "CAN1") (pin "VCC") (pinfunction "VCC_VCC") (pintype "bidirectional"))
      (node (ref "D3") (pin "P$1") (pinfunction "P$1_P$1") (pintype "bidirectional"))
      (node (ref "E1") (pin "3") (pinfunction "3_3") (pintype "bidirectional"))
      (node (ref "E1") (pin "4") (pinfunction "4_4") (pintype "bidirectional"))
      (node (ref "F10") (pin "1") (pinfunction "1_1") (pintype "passive"))
    )
    (net (code "7") (name "AUX12") (class "Default")
      (node (ref "ETH1") (pin "P$5") (pinfunction "5_P$5") (pintype "bidirectional"))
      (node (ref "ETH6") (pin "P$1") (pinfunction "1_P$1") (pintype "bidirectional"))
      (node (ref "F4") (pin "1") (pinfunction "1_1") (pintype "passive"))
      (node (ref "F9") (pin "1") (pinfunction "1_1") (pintype "passive"))
    )
    (net (code "8") (name "CAPCURR") (class "Default")
      (node (ref "ETH2") (pin "P$1") (pinfunction "1_P$1") (pintype "bidirectional"))
      (node (ref "R5") (pin "1") (pinfunction "1_1") (pintype "passive"))
      (node (ref "T1") (pin "17/A3") (pinfunction "17/A3/T_17/A3") (pintype "bidirectional"))
    )
    (net (code "9") (name "CAPVOLT") (class "Default")
      (node (ref "ETH2") (pin "P$3") (pinfunction "3_P$3") (pintype "bidirectional"))
      (node (ref "R7") (pin "1") (pinfunction "1_1") (pintype "passive"))
      (node (ref "T1") (pin "14/A0") (pinfunction "14/A0_14/A0") (pintype "bidirectional"))
    )
    (net (code "10") (name "CAP_R") (class "Default")
      (node (ref "IC1") (pin "8") (pinfunction "I0_8") (pintype "input"))
      (node (ref "T1") (pin "11") (pinfunction "11/MOSI_11") (pintype "bidirectional"))
    )
    (net (code "11") (name "CAP_R_OUT") (class "Default")
      (node (ref "ETH1") (pin "P$3") (pinfunction "3_P$3") (pintype "bidirectional"))
      (node (ref "IC1") (pin "10") (pinfunction "O_10") (pintype "output"))
    )
    (net (code "12") (name "CHARGE_R") (class "Default")
      (node (ref "IC1") (pin "12") (pinfunction "I0_12") (pintype "input"))
      (node (ref "T1") (pin "12") (pinfunction "12/MISO_12") (pintype "bidirectional"))
    )
    (net (code "13") (name "CHARGE_R_OUT") (class "Default")
      (node (ref "ETH1") (pin "P$4") (pinfunction "4_P$4") (pintype "bidirectional"))
      (node (ref "IC1") (pin "11") (pinfunction "O_11") (pintype "output"))
    )
    (net (code "14") (name "CVMRX") (class "Default")
      (node (ref "U2") (pin "9") (pinfunction "ROUT_9") (pintype "output"))
      (node (ref "U3") (pin "30") (pinfunction "PD0(RXD)_30") (pintype "bidirectional"))
    )
    (net (code "15") (name "CVMRX12") (class "Default")
      (node (ref "ETH3") (pin "P$3") (pinfunction "3_P$3") (pintype "bidirectional"))
      (node (ref "U2") (pin "8") (pinfunction "RIN_8") (pintype "input"))
    )
    (net (code "16") (name "CVMSIG1") (class "Default")
      (node (ref "ETH3") (pin "P$5") (pinfunction "5_P$5") (pintype "bidirectional"))
      (node (ref "R13") (pin "2") (pinfunction "2_2") (pintype "passive"))
      (node (ref "U1") (pin "6") (pinfunction "1C0_6") (pintype "input"))
    )
    (net (code "17") (name "CVMSIG2") (class "Default")
      (node (ref "ETH3") (pin "P$6") (pinfunction "6_P$6") (pintype "bidirectional"))
      (node (ref "R12") (pin "2") (pinfunction "2_2") (pintype "passive"))
      (node (ref "U1") (pin "5") (pinfunction "1C1_5") (pintype "input"))
    )
    (net (code "18") (name "CVMSIG3") (class "Default")
      (node (ref "ETH3") (pin "P$7") (pinfunction "7_P$7") (pintype "bidirectional"))
      (node (ref "R11") (pin "2") (pinfunction "2_2") (pintype "passive"))
      (node (ref "U1") (pin "4") (pinfunction "1C2_4") (pintype "input"))
    )
    (net (code "19") (name "CVMSIG4") (class "Default")
      (node (ref "ETH3") (pin "P$8") (pinfunction "8_P$8") (pintype "bidirectional"))
      (node (ref "R10") (pin "2") (pinfunction "2_2") (pintype "passive"))
      (node (ref "U1") (pin "3") (pinfunction "1C3_3") (pintype "input"))
    )
    (net (code "20") (name "CVMTX") (class "Default")
      (node (ref "U2") (pin "11") (pinfunction "DIN_11") (pintype "input"))
      (node (ref "U3") (pin "31") (pinfunction "PD1(TXD)_31") (pintype "bidirectional"))
    )
    (net (code "21") (name "CVMTX12") (class "Default")
      (node (ref "ETH3") (pin "P$2") (pinfunction "2_P$2") (pintype "bidirectional"))
      (node (ref "U2") (pin "13") (pinfunction "DOUT_13") (pintype "output"))
    )
    (net (code "22") (name "CVM_SER_INVALID") (class "Default")
      (node (ref "U2") (pin "10") (pinfunction "~{INVALID}_10") (pintype "output"))
      (node (ref "U3") (pin "1") (pinfunction "PD3(INT1)_1") (pintype "bidirectional"))
    )
    (net (code "23") (name "EXTRA_SIG") (class "Default")
      (node (ref "ETH7") (pin "P$2") (pinfunction "2_P$2") (pintype "bidirectional"))
      (node (ref "R21") (pin "2") (pinfunction "2_2") (pintype "passive"))
      (node (ref "U1") (pin "11") (pinfunction "2C1_11") (pintype "input"))
    )
    (net (code "24") (name "EXTRA_V") (class "Default")
      (node (ref "M1") (pin "IN3") (pinfunction "IN3_IN3") (pintype "bidirectional"))
      (node (ref "T1") (pin "10") (pinfunction "10/TX2/PWM_10") (pintype "bidirectional"))
    )
    (net (code "25") (name "EXTRA_V_G") (class "Default")
      (node (ref "ETH6") (pin "P$6") (pinfunction "6_P$6") (pintype "bidirectional"))
      (node (ref "M1") (pin "OUT3") (pinfunction "OUT3_OUT3") (pintype "bidirectional"))
      (node (ref "R15") (pin "2") (pinfunction "2_2") (pintype "passive"))
    )
    (net (code "26") (name "FC5") (class "Default")
      (node (ref "C18") (pin "+") (pinfunction "+_+") (pintype "passive"))
      (node (ref "C24") (pin "1") (pinfunction "1_1") (pintype "passive"))
      (node (ref "C25") (pin "+") (pinfunction "+_+") (pintype "passive"))
      (node (ref "C26") (pin "1") (pinfunction "1_1") (pintype "passive"))
      (node (ref "D2") (pin "P$1") (pinfunction "P$1_P$1") (pintype "bidirectional"))
      (node (ref "ETH2") (pin "P$5") (pinfunction "5_P$5") (pintype "bidirectional"))
      (node (ref "F2") (pin "2") (pinfunction "2_2") (pintype "passive"))
      (node (ref "F3") (pin "1") (pinfunction "1_1") (pintype "passive"))
      (node (ref "F6") (pin "1") (pinfunction "1_1") (pintype "passive"))
      (node (ref "F7") (pin "1") (pinfunction "1_1") (pintype "passive"))
      (node (ref "M1") (pin "VDD") (pinfunction "V+_VDD") (pintype "bidirectional"))
      (node (ref "O1") (pin "P$4") (pinfunction "RAW_P$4") (pintype "bidirectional"))
      (node (ref "U1") (pin "16") (pinfunction "VCC_16") (pintype "power_in"))
    )
    (net (code "27") (name "FC12") (class "Default")
      (node (ref "ETH1") (pin "P$6") (pinfunction "6_P$6") (pintype "bidirectional"))
      (node (ref "ETH5") (pin "P$1") (pinfunction "1_P$1") (pintype "bidirectional"))
      (node (ref "ETH6") (pin "P$3") (pinfunction "3_P$3") (pintype "bidirectional"))
      (node (ref "ETH6") (pin "P$5") (pinfunction "5_P$5") (pintype "bidirectional"))
      (node (ref "F5") (pin "1") (pinfunction "1_1") (pintype "passive"))
      (node (ref "F8") (pin "1") (pinfunction "1_1") (pintype "passive"))
    )
    (net (code "28") (name "FCCURR") (class "Default")
      (node (ref "ETH2") (pin "P$2") (pinfunction "2_P$2") (pintype "bidirectional"))
      (node (ref "R6") (pin "1") (pinfunction "1_1") (pintype "passive"))
      (node (ref "T1") (pin "15/A1") (pinfunction "15/A1/T_15/A1") (pintype "bidirectional"))
    )
    (net (code "29") (name "FCC_R") (class "Default")
      (node (ref "ETH2") (pin "P$6") (pinfunction "6_P$6") (pintype "bidirectional"))
      (node (ref "T1") (pin "20/A6") (pinfunction "20/A6/PWM_20/A6") (pintype "bidirectional"))
    )
    (net (code "30") (name "FCPRES") (class "Default")
      (node (ref "R18") (pin "2") (pinfunction "2_2") (pintype "passive"))
      (node (ref "R19") (pin "2") (pinfunction "2_2") (pintype "passive"))
      (node (ref "T1") (pin "A11") (pinfunction "A11_A11") (pintype "bidirectional"))
    )
    (net (code "31") (name "FCVOLT") (class "Default")
      (node (ref "ETH2") (pin "P$4") (pinfunction "4_P$4") (pintype "bidirectional"))
      (node (ref "R8") (pin "1") (pinfunction "1_1") (pintype "passive"))
      (node (ref "T1") (pin "16/A2") (pinfunction "16/A2/T_16/A2") (pintype "bidirectional"))
    )
    (net (code "32") (name "GND") (class "Default")
      (node (ref "C10") (pin "2") (pinfunction "2_2") (pintype "passive"))
      (node (ref "C11") (pin "2") (pinfunction "2_2") (pintype "passive"))
      (node (ref "C12") (pin "2") (pinfunction "2_2") (pintype "passive"))
      (node (ref "C14") (pin "2") (pinfunction "2_2") (pintype "passive"))
      (node (ref "C15") (pin "2") (pinfunction "2_2") (pintype "passive"))
      (node (ref "C17") (pin "-") (pinfunction "-_-") (pintype "passive"))
      (node (ref "C18") (pin "-") (pinfunction "-_-") (pintype "passive"))
      (node (ref "C19") (pin "2") (pinfunction "2_2") (pintype "passive"))
      (node (ref "C2") (pin "2") (pinfunction "2_2") (pintype "passive"))
      (node (ref "C20") (pin "2") (pinfunction "2_2") (pintype "passive"))
      (node (ref "C21") (pin "-") (pinfunction "-_-") (pintype "passive"))
      (node (ref "C22") (pin "2") (pinfunction "2_2") (pintype "passive"))
      (node (ref "C23") (pin "2") (pinfunction "2_2") (pintype "passive"))
      (node (ref "C24") (pin "2") (pinfunction "2_2") (pintype "passive"))
      (node (ref "C25") (pin "-") (pinfunction "-_-") (pintype "passive"))
      (node (ref "C26") (pin "2") (pinfunction "2_2") (pintype "passive"))
      (node (ref "C3") (pin "2") (pinfunction "2_2") (pintype "passive"))
      (node (ref "C4") (pin "2") (pinfunction "2_2") (pintype "passive"))
      (node (ref "C5") (pin "2") (pinfunction "2_2") (pintype "passive"))
      (node (ref "C7") (pin "2") (pinfunction "2_2") (pintype "passive"))
      (node (ref "C8") (pin "2") (pinfunction "2_2") (pintype "passive"))
      (node (ref "C9") (pin "2") (pinfunction "2_2") (pintype "passive"))
      (node (ref "CAN1") (pin "GND") (pinfunction "GND_GND") (pintype "bidirectional"))
      (node (ref "CAN1") (pin "GND_") (pinfunction "GND__GND_") (pintype "bidirectional"))
      (node (ref "D1") (pin "A") (pinfunction "A_A") (pintype "passive"))
      (node (ref "D2") (pin "P$2") (pinfunction "P$2_P$2") (pintype "bidirectional"))
      (node (ref "D3") (pin "P$2") (pinfunction "P$2_P$2") (pintype "bidirectional"))
      (node (ref "E1") (pin "5") (pinfunction "5_5") (pintype "bidirectional"))
      (node (ref "E1") (pin "6") (pinfunction "6_6") (pintype "bidirectional"))
      (node (ref "E1") (pin "SH1") (pinfunction "SH1_SH1") (pintype "bidirectional"))
      (node (ref "E1") (pin "SH2") (pinfunction "SH2_SH2") (pintype "bidirectional"))
      (node (ref "E2") (pin "5") (pinfunction "5_5") (pintype "bidirectional"))
      (node (ref "E2") (pin "6") (pinfunction "6_6") (pintype "bidirectional"))
      (node (ref "E2") (pin "SH1") (pinfunction "SH1_SH1") (pintype "bidirectional"))
      (node (ref "E2") (pin "SH2") (pinfunction "SH2_SH2") (pintype "bidirectional"))
      (node (ref "ETH1") (pin "P$13") (pinfunction "SHD1_P$13") (pintype "bidirectional"))
      (node (ref "ETH1") (pin "P$14") (pinfunction "SHD2_P$14") (pintype "bidirectional"))
      (node (ref "ETH1") (pin "P$7") (pinfunction "7_P$7") (pintype "bidirectional"))
      (node (ref "ETH1") (pin "P$8") (pinfunction "8_P$8") (pintype "bidirectional"))
      (node (ref "ETH2") (pin "P$13") (pinfunction "SHD1_P$13") (pintype "bidirectional"))
      (node (ref "ETH2") (pin "P$14") (pinfunction "SHD2_P$14") (pintype "bidirectional"))
      (node (ref "ETH2") (pin "P$7") (pinfunction "7_P$7") (pintype "bidirectional"))
      (node (ref "ETH2") (pin "P$8") (pinfunction "8_P$8") (pintype "bidirectional"))
      (node (ref "ETH3") (pin "P$13") (pinfunction "SHD1_P$13") (pintype "bidirectional"))
      (node (ref "ETH3") (pin "P$14") (pinfunction "SHD2_P$14") (pintype "bidirectional"))
      (node (ref "ETH3") (pin "P$4") (pinfunction "4_P$4") (pintype "bidirectional"))
      (node (ref "ETH4") (pin "P$13") (pinfunction "SHD1_P$13") (pintype "bidirectional"))
      (node (ref "ETH4") (pin "P$14") (pinfunction "SHD2_P$14") (pintype "bidirectional"))
      (node (ref "ETH4") (pin "P$8") (pinfunction "8_P$8") (pintype "bidirectional"))
      (node (ref "ETH5") (pin "P$13") (pinfunction "SHD1_P$13") (pintype "bidirectional"))
      (node (ref "ETH5") (pin "P$14") (pinfunction "SHD2_P$14") (pintype "bidirectional"))
      (node (ref "ETH5") (pin "P$2") (pinfunction "2_P$2") (pintype "bidirectional"))
      (node (ref "ETH6") (pin "P$13") (pinfunction "SHD1_P$13") (pintype "bidirectional"))
      (node (ref "ETH6") (pin "P$14") (pinfunction "SHD2_P$14") (pintype "bidirectional"))
      (node (ref "ETH7") (pin "P$13") (pinfunction "SHD1_P$13") (pintype "bidirectional"))
      (node (ref "ETH7") (pin "P$14") (pinfunction "SHD2_P$14") (pintype "bidirectional"))
      (node (ref "ETH7") (pin "P$5") (pinfunction "5_P$5") (pintype "bidirectional"))
      (node (ref "FAN1") (pin "GND") (pinfunction "GND_GND") (pintype "bidirectional"))
      (node (ref "FAN1") (pin "GND2") (pinfunction "GND_GND2") (pintype "bidirectional"))
      (node (ref "FAN1") (pin "GND3") (pinfunction "GND_GND3") (pintype "bidirectional"))
      (node (ref "ISP1") (pin "6") (pinfunction "GND_6") (pintype "power_in"))
      (node (ref "ISP2") (pin "6") (pinfunction "GND_6") (pintype "power_in"))
      (node (ref "ISP3") (pin "6") (pinfunction "GND_6") (pintype "power_in"))
      (node (ref "LCD1") (pin "GND1") (pinfunction "GND_GND1") (pintype "bidirectional"))
      (node (ref "LCD1") (pin "GND10") (pinfunction "GND_GND10") (pintype "bidirectional"))
      (node (ref "LCD1") (pin "GND11") (pinfunction "GND_GND11") (pintype "bidirectional"))
      (node (ref "LCD1") (pin "GND12") (pinfunction "GND_GND12") (pintype "bidirectional"))
      (node (ref "LCD1") (pin "GND13") (pinfunction "GND_GND13") (pintype "bidirectional"))
      (node (ref "LCD1") (pin "GND2") (pinfunction "GND_GND2") (pintype "bidirectional"))
      (node (ref "LCD1") (pin "GND3") (pinfunction "GND_GND3") (pintype "bidirectional"))
      (node (ref "LCD1") (pin "GND4") (pinfunction "GND_GND4") (pintype "bidirectional"))
      (node (ref "LCD1") (pin "GND5") (pinfunction "GND_GND5") (pintype "bidirectional"))
      (node (ref "LCD1") (pin "GND6") (pinfunction "GND_GND6") (pintype "bidirectional"))
      (node (ref "LCD1") (pin "GND7") (pinfunction "GND_GND7") (pintype "bidirectional"))
      (node (ref "LCD1") (pin "GND8") (pinfunction "GND_GND8") (pintype "bidirectional"))
      (node (ref "LCD1") (pin "GND9") (pinfunction "GND_GND9") (pintype "bidirectional"))
      (node (ref "LED1") (pin "C") (pinfunction "C_C") (pintype "passive"))
      (node (ref "LED10") (pin "C") (pinfunction "C_C") (pintype "passive"))
      (node (ref "LED11") (pin "C") (pinfunction "C_C") (pintype "passive"))
      (node (ref "LED12") (pin "C") (pinfunction "C_C") (pintype "passive"))
      (node (ref "LED2") (pin "C") (pinfunction "C_C") (pintype "passive"))
      (node (ref "LED3") (pin "C") (pinfunction "C_C") (pintype "passive"))
      (node (ref "LED4") (pin "C") (pinfunction "C_C") (pintype "passive"))
      (node (ref "LED5") (pin "C") (pinfunction "C_C") (pintype "passive"))
      (node (ref "LED6") (pin "C") (pinfunction "C_C") (pintype "passive"))
      (node (ref "LED7") (pin "C") (pinfunction "C_C") (pintype "passive"))
      (node (ref "LED8") (pin "C") (pinfunction "C_C") (pintype "passive"))
      (node (ref "LED9") (pin "C") (pinfunction "C_C") (pintype "passive"))
      (node (ref "M1") (pin "GND") (pinfunction "GND_GND") (pintype "bidirectional"))
      (node (ref "M1") (pin "GND1") (pinfunction "GND_GND1") (pintype "bidirectional"))
      (node (ref "M1") (pin "GND2") (pinfunction "GND_GND2") (pintype "bidirectional"))
      (node (ref "M1") (pin "VSS") (pinfunction "GND_VSS") (pintype "bidirectional"))
      (node (ref "O1") (pin "P$5") (pinfunction "GND_P$5") (pintype "bidirectional"))
      (node (ref "O1") (pin "P$6") (pinfunction "GND2_P$6") (pintype "bidirectional"))
      (node (ref "R1") (pin "2") (pinfunction "2_2") (pintype "passive"))
      (node (ref "R10") (pin "1") (pinfunction "1_1") (pintype "passive"))
      (node (ref "R11") (pin "1") (pinfunction "1_1") (pintype "passive"))
      (node (ref "R12") (pin "1") (pinfunction "1_1") (pintype "passive"))
      (node (ref "R13") (pin "1") (pinfunction "1_1") (pintype "passive"))
      (node (ref "R15") (pin "1") (pinfunction "1_1") (pintype "passive"))
      (node (ref "R16") (pin "1") (pinfunction "1_1") (pintype "passive"))
      (node (ref "R17") (pin "1") (pinfunction "1_1") (pintype "passive"))
      (node (ref "R18") (pin "1") (pinfunction "1_1") (pintype "passive"))
      (node (ref "R2") (pin "1") (pinfunction "1_1") (pintype "passive"))
      (node (ref "R20") (pin "1") (pinfunction "1_1") (pintype "passive"))
      (node (ref "R21") (pin "1") (pinfunction "1_1") (pintype "passive"))
      (node (ref "R7") (pin "2") (pinfunction "2_2") (pintype "passive"))
      (node (ref "R8") (pin "2") (pinfunction "2_2") (pintype "passive"))
      (node (ref "RTC1") (pin "P$2") (pinfunction "GND_P$2") (pintype "bidirectional"))
      (node (ref "S1") (pin "P$1") (pinfunction "P$1_P$1") (pintype "bidirectional"))
      (node (ref "S1") (pin "P$2") (pinfunction "P$1_P$2") (pintype "bidirectional"))
      (node (ref "S2") (pin "P$1") (pinfunction "P$1_P$1") (pintype "bidirectional"))
      (node (ref "S2") (pin "P$2") (pinfunction "P$1_P$2") (pintype "bidirectional"))
      (node (ref "SHT1") (pin "GND") (pinfunction "GND_GND") (pintype "bidirectional"))
      (node (ref "SJ1") (pin "1") (pinfunction "1_1") (pintype "passive"))
      (node (ref "T1") (pin "AGND") (pinfunction "AGND_AGND") (pintype "power_in"))
      (node (ref "T1") (pin "GND") (pinfunction "GND_GND") (pintype "power_in"))
      (node (ref "T1") (pin "GND1") (pinfunction "GND_GND1") (pintype "power_in"))
      (node (ref "U1") (pin "1") (pinfunction "1~{G}_1") (pintype "input"))
      (node (ref "U1") (pin "15") (pinfunction "2~{G}_15") (pintype "input"))
      (node (ref "U1") (pin "8") (pinfunction "GND_8") (pintype "passive"))
      (node (ref "U2") (pin "1") (pinfunction "~{EN}_1") (pintype "input"))
      (node (ref "U2") (pin "12") (pinfunction "FORCEON_12") (pintype "input"))
      (node (ref "U2") (pin "14") (pinfunction "GND_14") (pintype "passive"))
      (node (ref "U3") (pin "21") (pinfunction "AGND_21") (pintype "bidirectional"))
      (node (ref "U3") (pin "3") (pinfunction "GND_3") (pintype "bidirectional"))
      (node (ref "U3") (pin "5") (pinfunction "GND_5") (pintype "bidirectional"))
      (node (ref "U4") (pin "21") (pinfunction "AGND_21") (pintype "bidirectional"))
      (node (ref "U4") (pin "3") (pinfunction "GND_3") (pintype "bidirectional"))
      (node (ref "U4") (pin "5") (pinfunction "GND_5") (pintype "bidirectional"))
      (node (ref "U5") (pin "1") (pinfunction "~{EN}_1") (pintype "input"))
      (node (ref "U5") (pin "12") (pinfunction "FORCEON_12") (pintype "input"))
      (node (ref "U5") (pin "14") (pinfunction "GND_14") (pintype "passive"))
      (node (ref "U6") (pin "21") (pinfunction "AGND_21") (pintype "bidirectional"))
      (node (ref "U6") (pin "3") (pinfunction "GND_3") (pintype "bidirectional"))
      (node (ref "U6") (pin "5") (pinfunction "GND_5") (pintype "bidirectional"))
    )
    (net (code "33") (name "H2_OK") (class "Default")
      (node (ref "ETH7") (pin "P$1") (pinfunction "1_P$1") (pintype "bidirectional"))
      (node (ref "IC1") (pin "13") (pinfunction "I1_13") (pintype "input"))
      (node (ref "IC1") (pin "2") (pinfunction "I1_2") (pintype "input"))
      (node (ref "IC1") (pin "6") (pinfunction "I1_6") (pintype "input"))
      (node (ref "IC1") (pin "9") (pinfunction "I1_9") (pintype "input"))
      (node (ref "M1") (pin "ESTOP") (pinfunction "ESTOP_ESTOP") (pintype "bidirectional"))
      (node (ref "R20") (pin "2") (pinfunction "2_2") (pintype "passive"))
      (node (ref "U1") (pin "10") (pinfunction "2C0_10") (pintype "input"))
    )
    (net (code "34") (name "MISO1") (class "Default")
      (node (ref "ISP1") (pin "1") (pinfunction "MISO_1") (pintype "input"))
      (node (ref "U3") (pin "16") (pinfunction "PB4(MISO)_16") (pintype "bidirectional"))
    )
    (net (code "35") (name "MISO2") (class "Default")
      (node (ref "ISP2") (pin "1") (pinfunction "MISO_1") (pintype "input"))
      (node (ref "U4") (pin "16") (pinfunction "PB4(MISO)_16") (pintype "bidirectional"))
    )
    (net (code "36") (name "MISO3") (class "Default")
      (node (ref "ISP3") (pin "1") (pinfunction "MISO_1") (pintype "input"))
      (node (ref "U6") (pin "16") (pinfunction "PB4(MISO)_16") (pintype "bidirectional"))
    )
    (net (code "37") (name "MOSI1") (class "Default")
      (node (ref "ISP1") (pin "4") (pinfunction "MOSI_4") (pintype "output"))
      (node (ref "U3") (pin "15") (pinfunction "PB3(MOSI/OC2)_15") (pintype "bidirectional"))
    )
    (net (code "38") (name "MOSI2") (class "Default")
      (node (ref "ISP2") (pin "4") (pinfunction "MOSI_4") (pintype "output"))
      (node (ref "U4") (pin "15") (pinfunction "PB3(MOSI/OC2)_15") (pintype "bidirectional"))
    )
    (net (code "39") (name "MOSI3") (class "Default")
      (node (ref "ISP3") (pin "4") (pinfunction "MOSI_4") (pintype "output"))
      (node (ref "U6") (pin "15") (pinfunction "PB3(MOSI/OC2)_15") (pintype "bidirectional"))
    )
    (net (code "40") (name "MOTOR_R") (class "Default")
      (node (ref "IC1") (pin "5") (pinfunction "I0_5") (pintype "input"))
      (node (ref "T1") (pin "22/A8") (pinfunction "22/A8/T/PWM_22/A8") (pintype "bidirectional"))
    )
    (net (code "41") (name "MOTOR_R_OUT") (class "Default")
      (node (ref "ETH1") (pin "P$2") (pinfunction "2_P$2") (pintype "bidirectional"))
      (node (ref "IC1") (pin "4") (pinfunction "O_4") (pintype "output"))
    )
    (net (code "42") (name "MRX") (class "Default")
      (node (ref "U4") (pin "30") (pinfunction "PD0(RXD)_30") (pintype "bidirectional"))
      (node (ref "U5") (pin "9") (pinfunction "ROUT_9") (pintype "output"))
    )
    (net (code "43") (name "MRX12") (class "Default")
      (node (ref "ETH4") (pin "P$2") (pinfunction "2_P$2") (pintype "bidirectional"))
      (node (ref "U5") (pin "8") (pinfunction "RIN_8") (pintype "input"))
    )
    (net (code "44") (name "MTX") (class "Default")
      (node (ref "U4") (pin "31") (pinfunction "PD1(TXD)_31") (pintype "bidirectional"))
      (node (ref "U5") (pin "11") (pinfunction "DIN_11") (pintype "input"))
    )
    (net (code "45") (name "MTX12") (class "Default")
      (node (ref "ETH4") (pin "P$1") (pinfunction "1_P$1") (pintype "bidirectional"))
      (node (ref "U5") (pin "13") (pinfunction "DOUT_13") (pintype "output"))
    )
    (net (code "46") (name "MULTA") (class "Default")
      (node (ref "T1") (pin "3") (pinfunction "3/CAN-TX/PWM_3") (pintype "bidirectional"))
      (node (ref "U1") (pin "14") (pinfunction "A_14") (pintype "input"))
    )
    (net (code "47") (name "MULTB") (class "Default")
      (node (ref "T1") (pin "4") (pinfunction "4/CAN-RX-PWM_4") (pintype "bidirectional"))
      (node (ref "U1") (pin "2") (pinfunction "B_2") (pintype "input"))
    )
    (net (code "48") (name "MULTO1") (class "Default")
      (node (ref "R1") (pin "1") (pinfunction "1_1") (pintype "passive"))
      (node (ref "T1") (pin "5") (pinfunction "5/PWM_5") (pintype "bidirectional"))
      (node (ref "U1") (pin "7") (pinfunction "1Y_7") (pintype "output"))
    )
    (net (code "49") (name "MULTO2") (class "Default")
      (node (ref "R2") (pin "2") (pinfunction "2_2") (pintype "passive"))
      (node (ref "T1") (pin "2") (pinfunction "2_2") (pintype "bidirectional"))
      (node (ref "U1") (pin "9") (pinfunction "2Y_9") (pintype "output"))
    )
    (net (code "50") (name "M_SER_INVALID") (class "Default")
      (node (ref "U4") (pin "1") (pinfunction "PD3(INT1)_1") (pintype "bidirectional"))
      (node (ref "U5") (pin "10") (pinfunction "~{INVALID}_10") (pintype "output"))
    )
    (net (code "51") (name "M_SIG_1") (class "Default")
      (node (ref "ETH4") (pin "P$6") (pinfunction "6_P$6") (pintype "bidirectional"))
      (node (ref "U1") (pin "12") (pinfunction "2C2_12") (pintype "input"))
    )
    (net (code "52") (name "M_SIG_2") (class "Default")
      (node (ref "ETH4") (pin "P$7") (pinfunction "7_P$7") (pintype "bidirectional"))
      (node (ref "U1") (pin "13") (pinfunction "2C3_13") (pintype "input"))
    )
    (net (code "53") (name "Net-(E1-Pad1)") (class "Default")
      (node (ref "E1") (pin "1") (pinfunction "1_1") (pintype "bidirectional"))
      (node (ref "E1") (pin "2") (pinfunction "2_2") (pintype "bidirectional"))
      (node (ref "F4") (pin "2") (pinfunction "2_2") (pintype "passive"))
    )
    (net (code "54") (name "Net-(E2-Pad1)") (class "Default")
      (node (ref "E2") (pin "1") (pinfunction "1_1") (pintype "bidirectional"))
      (node (ref "E2") (pin "2") (pinfunction "2_2") (pintype "bidirectional"))
      (node (ref "F5") (pin "2") (pinfunction "2_2") (pintype "passive"))
    )
    (net (code "55") (name "Net-(E2-Pad3)") (class "Default")
      (node (ref "E2") (pin "3") (pinfunction "3_3") (pintype "bidirectional"))
      (node (ref "E2") (pin "4") (pinfunction "4_4") (pintype "bidirectional"))
      (node (ref "F6") (pin "2") (pinfunction "2_2") (pintype "passive"))
    )
    (net (code "56") (name "Net-(ETH3-1)") (class "Default")
      (node (ref "ETH3") (pin "P$1") (pinfunction "1_P$1") (pintype "bidirectional"))
      (node (ref "F3") (pin "2") (pinfunction "2_2") (pintype "passive"))
    )
    (net (code "57") (name "Net-(ETH5-3)") (class "Default")
      (node (ref "ETH5") (pin "P$3") (pinfunction "3_P$3") (pintype "bidirectional"))
      (node (ref "R19") (pin "1") (pinfunction "1_1") (pintype "passive"))
    )
    (net (code "58") (name "Net-(ETH7-6)") (class "Default")
      (node (ref "ETH7") (pin "P$6") (pinfunction "6_P$6") (pintype "bidirectional"))
      (node (ref "F9") (pin "2") (pinfunction "2_2") (pintype "passive"))
    )
    (net (code "59") (name "Net-(ETH7-8)") (class "Default")
      (node (ref "ETH7") (pin "P$8") (pinfunction "8_P$8") (pintype "bidirectional"))
      (node (ref "F10") (pin "2") (pinfunction "2_2") (pintype "passive"))
    )
    (net (code "60") (name "Net-(F1-Pad1)") (class "Default")
      (node (ref "F1") (pin "1") (pinfunction "1_1") (pintype "passive"))
      (node (ref "T1") (pin "3.3V") (pinfunction "3.3V_3.3V") (pintype "power_in"))
      (node (ref "T1") (pin "3.3V1") (pinfunction "3.3V_3.3V1") (pintype "power_in"))
    )
    (net (code "61") (name "Net-(F2-Pad1)") (class "Default")
      (node (ref "F2") (pin "1") (pinfunction "1_1") (pintype "passive"))
      (node (ref "T1") (pin "VIN") (pinfunction "VIN_VIN") (pintype "power_in"))
    )
    (net (code "62") (name "Net-(F7-Pad2)") (class "Default")
      (node (ref "F7") (pin "2") (pinfunction "2_2") (pintype "passive"))
      (node (ref "FAN1") (pin "5") (pinfunction "5V_5") (pintype "bidirectional"))
      (node (ref "FAN1") (pin "5_2") (pinfunction "5V_5_2") (pintype "bidirectional"))
    )
    (net (code "63") (name "Net-(F8-Pad2)") (class "Default")
      (node (ref "F8") (pin "2") (pinfunction "2_2") (pintype "passive"))
      (node (ref "FAN1") (pin "12") (pinfunction "12V_12") (pintype "bidirectional"))
      (node (ref "FAN1") (pin "12_2") (pinfunction "12V_12_2") (pintype "bidirectional"))
      (node (ref "FAN1") (pin "12_3") (pinfunction "12V_12_3") (pintype "bidirectional"))
    )
    (net (code "64") (name "Net-(LED1-PadA)") (class "Default")
      (node (ref "LED1") (pin "A") (pinfunction "A_A") (pintype "passive"))
      (node (ref "R23") (pin "1") (pinfunction "1_1") (pintype "passive"))
    )
    (net (code "65") (name "Net-(LED2-PadA)") (class "Default")
      (node (ref "LED2") (pin "A") (pinfunction "A_A") (pintype "passive"))
      (node (ref "R24") (pin "1") (pinfunction "1_1") (pintype "passive"))
    )
    (net (code "66") (name "Net-(LED3-PadA)") (class "Default")
      (node (ref "LED3") (pin "A") (pinfunction "A_A") (pintype "passive"))
      (node (ref "R25") (pin "1") (pinfunction "1_1") (pintype "passive"))
    )
    (net (code "67") (name "Net-(LED4-PadA)") (class "Default")
      (node (ref "LED4") (pin "A") (pinfunction "A_A") (pintype "passive"))
      (node (ref "R26") (pin "1") (pinfunction "1_1") (pintype "passive"))
    )
    (net (code "68") (name "Net-(LED5-PadA)") (class "Default")
      (node (ref "LED5") (pin "A") (pinfunction "A_A") (pintype "passive"))
      (node (ref "R27") (pin "1") (pinfunction "1_1") (pintype "passive"))
    )
    (net (code "69") (name "Net-(LED6-PadA)") (class "Default")
      (node (ref "LED6") (pin "A") (pinfunction "A_A") (pintype "passive"))
      (node (ref "R28") (pin "1") (pinfunction "1_1") (pintype "passive"))
    )
    (net (code "70") (name "Net-(LED7-PadA)") (class "Default")
      (node (ref "LED7") (pin "A") (pinfunction "A_A") (pintype "passive"))
      (node (ref "R29") (pin "1") (pinfunction "1_1") (pintype "passive"))
    )
    (net (code "71") (name "Net-(LED8-PadA)") (class "Default")
      (node (ref "LED8") (pin "A") (pinfunction "A_A") (pintype "passive"))
      (node (ref "R30") (pin "1") (pinfunction "1_1") (pintype "passive"))
    )
    (net (code "72") (name "Net-(LED9-PadA)") (class "Default")
      (node (ref "LED9") (pin "A") (pinfunction "A_A") (pintype "passive"))
      (node (ref "R31") (pin "1") (pinfunction "1_1") (pintype "passive"))
    )
    (net (code "73") (name "Net-(LED10-PadA)") (class "Default")
      (node (ref "LED10") (pin "A") (pinfunction "A_A") (pintype "passive"))
      (node (ref "R32") (pin "1") (pinfunction "1_1") (pintype "passive"))
    )
    (net (code "74") (name "Net-(LED11-PadA)") (class "Default")
      (node (ref "LED11") (pin "A") (pinfunction "A_A") (pintype "passive"))
      (node (ref "R33") (pin "1") (pinfunction "1_1") (pintype "passive"))
    )
    (net (code "75") (name "Net-(LED12-PadA)") (class "Default")
      (node (ref "LED12") (pin "A") (pinfunction "A_A") (pintype "passive"))
      (node (ref "R34") (pin "1") (pinfunction "1_1") (pintype "passive"))
    )
    (net (code "76") (name "Net-(U2-C1+)") (class "Default")
      (node (ref "C6") (pin "1") (pinfunction "1_1") (pintype "passive"))
      (node (ref "U2") (pin "2") (pinfunction "C1+_2") (pintype "passive"))
    )
    (net (code "77") (name "Net-(U2-C1-)") (class "Default")
      (node (ref "C6") (pin "2") (pinfunction "2_2") (pintype "passive"))
      (node (ref "U2") (pin "4") (pinfunction "C1-_4") (pintype "passive"))
    )
    (net (code "78") (name "Net-(U2-C2+)") (class "Default")
      (node (ref "C1") (pin "1") (pinfunction "1_1") (pintype "passive"))
      (node (ref "U2") (pin "5") (pinfunction "C2+_5") (pintype "passive"))
    )
    (net (code "79") (name "Net-(U2-C2-)") (class "Default")
      (node (ref "C1") (pin "2") (pinfunction "2_2") (pintype "passive"))
      (node (ref "U2") (pin "6") (pinfunction "C2-_6") (pintype "passive"))
    )
    (net (code "80") (name "Net-(U2-V+)") (class "Default")
      (node (ref "C3") (pin "1") (pinfunction "1_1") (pintype "passive"))
      (node (ref "U2") (pin "3") (pinfunction "V+_3") (pintype "power_in"))
    )
    (net (code "81") (name "Net-(U2-V-)") (class "Default")
      (node (ref "C4") (pin "1") (pinfunction "1_1") (pintype "passive"))
      (node (ref "U2") (pin "7") (pinfunction "V-_7") (pintype "power_in"))
    )
    (net (code "82") (name "Net-(U3-PB6(XTAL1{slash}TOSC1))") (class "Default")
      (node (ref "C7") (pin "1") (pinfunction "1_1") (pintype "passive"))
      (node (ref "U3") (pin "7") (pinfunction "PB6(XTAL1/TOSC1)_7") (pintype "bidirectional"))
      (node (ref "Y1") (pin "2") (pinfunction "2_2") (pintype "passive"))
    )
    (net (code "83") (name "Net-(U3-PB7(XTAL2{slash}TOSC2))") (class "Default")
      (node (ref "C8") (pin "1") (pinfunction "1_1") (pintype "passive"))
      (node (ref "U3") (pin "8") (pinfunction "PB7(XTAL2/TOSC2)_8") (pintype "bidirectional"))
      (node (ref "Y1") (pin "1") (pinfunction "1_1") (pintype "passive"))
    )
    (net (code "84") (name "Net-(U4-PB6(XTAL1{slash}TOSC1))") (class "Default")
      (node (ref "C11") (pin "1") (pinfunction "1_1") (pintype "passive"))
      (node (ref "U4") (pin "7") (pinfunction "PB6(XTAL1/TOSC1)_7") (pintype "bidirectional"))
      (node (ref "Y2") (pin "2") (pinfunction "2_2") (pintype "passive"))
    )
    (net (code "85") (name "Net-(U4-PB7(XTAL2{slash}TOSC2))") (class "Default")
      (node (ref "C12") (pin "1") (pinfunction "1_1") (pintype "passive"))
      (node (ref "U4") (pin "8") (pinfunction "PB7(XTAL2/TOSC2)_8") (pintype "bidirectional"))
      (node (ref "Y2") (pin "1") (pinfunction "1_1") (pintype "passive"))
    )
    (net (code "86") (name "Net-(U5-C1+)") (class "Default")
      (node (ref "C16") (pin "1") (pinfunction "1_1") (pintype "passive"))
      (node (ref "U5") (pin "2") (pinfunction "C1+_2") (pintype "passive"))
    )
    (net (code "87") (name "Net-(U5-C1-)") (class "Default")
      (node (ref "C16") (pin "2") (pinfunction "2_2") (pintype "passive"))
      (node (ref "U5") (pin "4") (pinfunction "C1-_4") (pintype "passive"))
    )
    (net (code "88") (name "Net-(U5-C2+)") (class "Default")
      (node (ref "C13") (pin "1") (pinfunction "1_1") (pintype "passive"))
      (node (ref "U5") (pin "5") (pinfunction "C2+_5") (pintype "passive"))
    )
    (net (code "89") (name "Net-(U5-C2-)") (class "Default")
      (node (ref "C13") (pin "2") (pinfunction "2_2") (pintype "passive"))
      (node (ref "U5") (pin "6") (pinfunction "C2-_6") (pintype "passive"))
    )
    (net (code "90") (name "Net-(U5-V+)") (class "Default")
      (node (ref "C14") (pin "1") (pinfunction "1_1") (pintype "passive"))
      (node (ref "U5") (pin "3") (pinfunction "V+_3") (pintype "power_in"))
    )
    (net (code "91") (name "Net-(U5-V-)") (class "Default")
      (node (ref "C15") (pin "1") (pinfunction "1_1") (pintype "passive"))
      (node (ref "U5") (pin "7") (pinfunction "V-_7") (pintype "power_in"))
    )
    (net (code "92") (name "Net-(U6-ADC6)") (class "Default")
      (node (ref "R27") (pin "2") (pinfunction "2_2") (pintype "passive"))
      (node (ref "U6") (pin "19") (pinfunction "ADC6_19") (pintype "bidirectional"))
    )
    (net (code "93") (name "Net-(U6-ADC7)") (class "Default")
      (node (ref "R28") (pin "2") (pinfunction "2_2") (pintype "passive"))
      (node (ref "U6") (pin "22") (pinfunction "ADC7_22") (pintype "bidirectional"))
    )
    (net (code "94") (name "Net-(U6-PC0(ADC0))") (class "Default")
      (node (ref "R23") (pin "2") (pinfunction "2_2") (pintype "passive"))
      (node (ref "U6") (pin "23") (pinfunction "PC0(ADC0)_23") (pintype "bidirectional"))
    )
    (net (code "95") (name "Net-(U6-PC1(ADC1))") (class "Default")
      (node (ref "R24") (pin "2") (pinfunction "2_2") (pintype "passive"))
      (node (ref "U6") (pin "24") (pinfunction "PC1(ADC1)_24") (pintype "bidirectional"))
    )
    (net (code "96") (name "Net-(U6-PC2(ADC2))") (class "Default")
      (node (ref "R25") (pin "2") (pinfunction "2_2") (pintype "passive"))
      (node (ref "U6") (pin "25") (pinfunction "PC2(ADC2)_25") (pintype "bidirectional"))
    )
    (net (code "97") (name "Net-(U6-PC3(ADC3))") (class "Default")
      (node (ref "R26") (pin "2") (pinfunction "2_2") (pintype "passive"))
      (node (ref "U6") (pin "26") (pinfunction "PC3(ADC3)_26") (pintype "bidirectional"))
    )
    (net (code "98") (name "Net-(U6-PD0(RXD))") (class "Default")
      (node (ref "R29") (pin "2") (pinfunction "2_2") (pintype "passive"))
      (node (ref "U6") (pin "30") (pinfunction "PD0(RXD)_30") (pintype "bidirectional"))
    )
    (net (code "99") (name "Net-(U6-PD1(TXD))") (class "Default")
      (node (ref "R30") (pin "2") (pinfunction "2_2") (pintype "passive"))
      (node (ref "U6") (pin "31") (pinfunction "PD1(TXD)_31") (pintype "bidirectional"))
    )
    (net (code "100") (name "Net-(U6-PD2(INT0))") (class "Default")
      (node (ref "R31") (pin "2") (pinfunction "2_2") (pintype "passive"))
      (node (ref "U6") (pin "32") (pinfunction "PD2(INT0)_32") (pintype "bidirectional"))
    )
    (net (code "101") (name "Net-(U6-PD3(INT1))") (class "Default")
      (node (ref "R32") (pin "2") (pinfunction "2_2") (pintype "passive"))
      (node (ref "U6") (pin "1") (pinfunction "PD3(INT1)_1") (pintype "bidirectional"))
    )
    (net (code "102") (name "Net-(U6-PD4(XCK{slash}T0))") (class "Default")
      (node (ref "R33") (pin "2") (pinfunction "2_2") (pintype "passive"))
      (node (ref "U6") (pin "2") (pinfunction "PD4(XCK/T0)_2") (pintype "bidirectional"))
    )
    (net (code "103") (name "Net-(U6-PD5(T1))") (class "Default")
      (node (ref "R34") (pin "2") (pinfunction "2_2") (pintype "passive"))
      (node (ref "U6") (pin "9") (pinfunction "PD5(T1)_9") (pintype "bidirectional"))
    )
    (net (code "104") (name "PURGE_V") (class "Default")
      (node (ref "M1") (pin "IN2") (pinfunction "IN2_IN2") (pintype "bidirectional"))
      (node (ref "T1") (pin "9") (pinfunction "9/RX2/PWM_9") (pintype "bidirectional"))
    )
    (net (code "105") (name "PURGE_V_G") (class "Default")
      (node (ref "ETH6") (pin "P$4") (pinfunction "4_P$4") (pintype "bidirectional"))
      (node (ref "M1") (pin "OUT2") (pinfunction "OUT2_OUT2") (pintype "bidirectional"))
      (node (ref "R16") (pin "2") (pinfunction "2_2") (pintype "passive"))
    )
    (net (code "106") (name "RX1") (class "Default")
      (node (ref "CAN1") (pin "TX0") (pinfunction "TX0_TX0") (pintype "bidirectional"))
      (node (ref "T1") (pin "0") (pinfunction "0/RX1/T_0") (pintype "bidirectional"))
    )
    (net (code "107") (name "RX3") (class "Default")
      (node (ref "O1") (pin "P$3") (pinfunction "TXO_P$3") (pintype "bidirectional"))
      (node (ref "T1") (pin "7") (pinfunction "7/RX3_7") (pintype "bidirectional"))
    )
    (net (code "108") (name "SCK1") (class "Default")
      (node (ref "ISP1") (pin "3") (pinfunction "SCK_3") (pintype "output"))
      (node (ref "U3") (pin "17") (pinfunction "PB5(SCK)_17") (pintype "bidirectional"))
    )
    (net (code "109") (name "SCK2") (class "Default")
      (node (ref "ISP2") (pin "3") (pinfunction "SCK_3") (pintype "output"))
      (node (ref "U4") (pin "17") (pinfunction "PB5(SCK)_17") (pintype "bidirectional"))
    )
    (net (code "110") (name "SCK3") (class "Default")
      (node (ref "ISP3") (pin "3") (pinfunction "SCK_3") (pintype "output"))
      (node (ref "U6") (pin "17") (pinfunction "PB5(SCK)_17") (pintype "bidirectional"))
    )
    (net (code "111") (name "SCL") (class "Default")
      (node (ref "FAN1") (pin "SCL") (pinfunction "SCL_SCL") (pintype "bidirectional"))
      (node (ref "LCD1") (pin "SCL") (pinfunction "SCL_SCL") (pintype "bidirectional"))
      (node (ref "R3") (pin "2") (pinfunction "2_2") (pintype "passive"))
      (node (ref "RTC1") (pin "P$3") (pinfunction "SCL_P$3") (pintype "bidirectional"))
      (node (ref "SHT1") (pin "SCL") (pinfunction "SCL_SCL") (pintype "bidirectional"))
      (node (ref "T1") (pin "19/A5") (pinfunction "19/A5/T/SCL0_19/A5") (pintype "bidirectional"))
      (node (ref "U3") (pin "28") (pinfunction "PC5(ADC5/SCL)_28") (pintype "bidirectional"))
      (node (ref "U4") (pin "28") (pinfunction "PC5(ADC5/SCL)_28") (pintype "bidirectional"))
      (node (ref "U6") (pin "28") (pinfunction "PC5(ADC5/SCL)_28") (pintype "bidirectional"))
    )
    (net (code "112") (name "SDA") (class "Default")
      (node (ref "FAN1") (pin "SDA") (pinfunction "SDA_SDA") (pintype "bidirectional"))
      (node (ref "LCD1") (pin "SDA") (pinfunction "SDA_SDA") (pintype "bidirectional"))
      (node (ref "R4") (pin "2") (pinfunction "2_2") (pintype "passive"))
      (node (ref "RTC1") (pin "P$4") (pinfunction "SDA_P$4") (pintype "bidirectional"))
      (node (ref "SHT1") (pin "SDA") (pinfunction "SDA_SDA") (pintype "bidirectional"))
      (node (ref "T1") (pin "18/A4") (pinfunction "18/A4/T/SDA0_18/A4") (pintype "bidirectional"))
      (node (ref "U3") (pin "27") (pinfunction "PC4(ADC4/SDA)_27") (pintype "bidirectional"))
      (node (ref "U4") (pin "27") (pinfunction "PC4(ADC4/SDA)_27") (pintype "bidirectional"))
      (node (ref "U6") (pin "27") (pinfunction "PC4(ADC4/SDA)_27") (pintype "bidirectional"))
    )
    (net (code "113") (name "START_R") (class "Default")
      (node (ref "IC1") (pin "1") (pinfunction "I0_1") (pintype "input"))
      (node (ref "T1") (pin "21/A7") (pinfunction "21/A7/PWM_21/A7") (pintype "bidirectional"))
    )
    (net (code "114") (name "START_R_OUT") (class "Default")
      (node (ref "ETH1") (pin "P$1") (pinfunction "1_P$1") (pintype "bidirectional"))
      (node (ref "IC1") (pin "3") (pinfunction "O_3") (pintype "output"))
    )
    (net (code "115") (name "SUPPLY_V") (class "Default")
      (node (ref "M1") (pin "IN1") (pinfunction "IN1_IN1") (pintype "bidirectional"))
      (node (ref "T1") (pin "6") (pinfunction "6/PWM_6") (pintype "bidirectional"))
    )
    (net (code "116") (name "SUPPLY_V_G") (class "Default")
      (node (ref "ETH6") (pin "P$2") (pinfunction "2_P$2") (pintype "bidirectional"))
      (node (ref "M1") (pin "OUT1") (pinfunction "OUT1_OUT1") (pintype "bidirectional"))
      (node (ref "R17") (pin "2") (pinfunction "2_2") (pintype "passive"))
    )
    (net (code "117") (name "THIS_IS_NOT_CONNECTED_1") (class "Default")
      (node (ref "ISP1") (pin "2") (pinfunction "VCC_2") (pintype "power_in"))
    )
    (net (code "118") (name "THIS_IS_NOT_CONNECTED_2") (class "Default")
      (node (ref "ISP2") (pin "2") (pinfunction "VCC_2") (pintype "power_in"))
    )
    (net (code "119") (name "THIS_IS_NOT_CONNECTED_3") (class "Default")
      (node (ref "ISP3") (pin "2") (pinfunction "VCC_2") (pintype "power_in"))
    )
    (net (code "120") (name "TX1") (class "Default")
      (node (ref "CAN1") (pin "RXI") (pinfunction "RXI_RXI") (pintype "bidirectional"))
      (node (ref "T1") (pin "1") (pinfunction "1/TX1/T_1") (pintype "bidirectional"))
    )
    (net (code "121") (name "TX3") (class "Default")
      (node (ref "O1") (pin "P$2") (pinfunction "RXI_P$2") (pintype "bidirectional"))
      (node (ref "T1") (pin "8") (pinfunction "8/TX3_8") (pintype "bidirectional"))
    )
    (net (code "122") (name "VBAT") (class "Default")
      (node (ref "T1") (pin "VBAT") (pinfunction "VBAT_VBAT") (pintype "power_in"))
    )
    (net (code "123") (name "VDD") (class "Default")
      (node (ref "SJ2") (pin "2") (pinfunction "2_2") (pintype "passive"))
    )
    (net (code "124") (name "VSS") (class "Default")
      (node (ref "SJ1") (pin "2") (pinfunction "2_2") (pintype "passive"))
    )
    (net (code "125") (name "VUSB") (class "Default")
      (node (ref "T1") (pin "VUSB") (pinfunction "VUSB_VUSB") (pintype "power_in"))
    )
    (net (code "126") (name "unconnected-(CAN1-PadCTS)") (class "Default")
      (node (ref "CAN1") (pin "CTS") (pinfunction "CTS_CTS") (pintype "bidirectional"))
    )
    (net (code "127") (name "unconnected-(CAN1-PadDTR)") (class "Default")
      (node (ref "CAN1") (pin "DTR") (pinfunction "DTR_DTR") (pintype "bidirectional"))
    )
    (net (code "128") (name "unconnected-(CAN1-PadSCL)") (class "Default")
      (node (ref "CAN1") (pin "SCL") (pinfunction "SCL_SCL") (pintype "bidirectional"))
    )
    (net (code "129") (name "unconnected-(CAN1-PadSDA)") (class "Default")
      (node (ref "CAN1") (pin "SDA") (pinfunction "SDA_SDA") (pintype "bidirectional"))
    )
    (net (code "130") (name "unconnected-(CAN1-PadVIN)") (class "Default")
      (node (ref "CAN1") (pin "VIN") (pinfunction "VIN_VIN") (pintype "bidirectional"))
    )
    (net (code "131") (name "unconnected-(ETH1-LED1N-PadP$9)") (class "Default")
      (node (ref "ETH1") (pin "P$9") (pinfunction "LED1N_P$9") (pintype "bidirectional"))
    )
    (net (code "132") (name "unconnected-(ETH1-LED1P-PadP$10)") (class "Default")
      (node (ref "ETH1") (pin "P$10") (pinfunction "LED1P_P$10") (pintype "bidirectional"))
    )
    (net (code "133") (name "unconnected-(ETH1-LED2N-PadP$11)") (class "Default")
      (node (ref "ETH1") (pin "P$11") (pinfunction "LED2N_P$11") (pintype "bidirectional"))
    )
    (net (code "134") (name "unconnected-(ETH1-LED2P-PadP$12)") (class "Default")
      (node (ref "ETH1") (pin "P$12") (pinfunction "LED2P_P$12") (pintype "bidirectional"))
    )
    (net (code "135") (name "unconnected-(ETH2-LED1N-PadP$9)") (class "Default")
      (node (ref "ETH2") (pin "P$9") (pinfunction "LED1N_P$9") (pintype "bidirectional"))
    )
    (net (code "136") (name "unconnected-(ETH2-LED1P-PadP$10)") (class "Default")
      (node (ref "ETH2") (pin "P$10") (pinfunction "LED1P_P$10") (pintype "bidirectional"))
    )
    (net (code "137") (name "unconnected-(ETH2-LED2N-PadP$11)") (class "Default")
      (node (ref "ETH2") (pin "P$11") (pinfunction "LED2N_P$11") (pintype "bidirectional"))
    )
    (net (code "138") (name "unconnected-(ETH2-LED2P-PadP$12)") (class "Default")
      (node (ref "ETH2") (pin "P$12") (pinfunction "LED2P_P$12") (pintype "bidirectional"))
    )
    (net (code "139") (name "unconnected-(ETH3-LED1N-PadP$9)") (class "Default")
      (node (ref "ETH3") (pin "P$9") (pinfunction "LED1N_P$9") (pintype "bidirectional"))
    )
    (net (code "140") (name "unconnected-(ETH3-LED1P-PadP$10)") (class "Default")
      (node (ref "ETH3") (pin "P$10") (pinfunction "LED1P_P$10") (pintype "bidirectional"))
    )
    (net (code "141") (name "unconnected-(ETH3-LED2N-PadP$11)") (class "Default")
      (node (ref "ETH3") (pin "P$11") (pinfunction "LED2N_P$11") (pintype "bidirectional"))
    )
    (net (code "142") (name "unconnected-(ETH3-LED2P-PadP$12)") (class "Default")
      (node (ref "ETH3") (pin "P$12") (pinfunction "LED2P_P$12") (pintype "bidirectional"))
    )
    (net (code "143") (name "unconnected-(ETH4-3-PadP$3)") (class "Default")
      (node (ref "ETH4") (pin "P$3") (pinfunction "3_P$3") (pintype "bidirectional"))
    )
    (net (code "144") (name "unconnected-(ETH4-4-PadP$4)") (class "Default")
      (node (ref "ETH4") (pin "P$4") (pinfunction "4_P$4") (pintype "bidirectional"))
    )
    (net (code "145") (name "unconnected-(ETH4-5-PadP$5)") (class "Default")
      (node (ref "ETH4") (pin "P$5") (pinfunction "5_P$5") (pintype "bidirectional"))
    )
    (net (code "146") (name "unconnected-(ETH4-LED1N-PadP$9)") (class "Default")
      (node (ref "ETH4") (pin "P$9") (pinfunction "LED1N_P$9") (pintype "bidirectional"))
    )
    (net (code "147") (name "unconnected-(ETH4-LED1P-PadP$10)") (class "Default")
      (node (ref "ETH4") (pin "P$10") (pinfunction "LED1P_P$10") (pintype "bidirectional"))
    )
    (net (code "148") (name "unconnected-(ETH4-LED2N-PadP$11)") (class "Default")
      (node (ref "ETH4") (pin "P$11") (pinfunction "LED2N_P$11") (pintype "bidirectional"))
    )
    (net (code "149") (name "unconnected-(ETH4-LED2P-PadP$12)") (class "Default")
      (node (ref "ETH4") (pin "P$12") (pinfunction "LED2P_P$12") (pintype "bidirectional"))
    )
    (net (code "150") (name "unconnected-(ETH5-4-PadP$4)") (class "Default")
      (node (ref "ETH5") (pin "P$4") (pinfunction "4_P$4") (pintype "bidirectional"))
    )
    (net (code "151") (name "unconnected-(ETH5-5-PadP$5)") (class "Default")
      (node (ref "ETH5") (pin "P$5") (pinfunction "5_P$5") (pintype "bidirectional"))
    )
    (net (code "152") (name "unconnected-(ETH5-6-PadP$6)") (class "Default")
      (node (ref "ETH5") (pin "P$6") (pinfunction "6_P$6") (pintype "bidirectional"))
    )
    (net (code "153") (name "unconnected-(ETH5-7-PadP$7)") (class "Default")
      (node (ref "ETH5") (pin "P$7") (pinfunction "7_P$7") (pintype "bidirectional"))
    )
    (net (code "154") (name "unconnected-(ETH5-8-PadP$8)") (class "Default")
      (node (ref "ETH5") (pin "P$8") (pinfunction "8_P$8") (pintype "bidirectional"))
    )
    (net (code "155") (name "unconnected-(ETH5-LED1N-PadP$9)") (class "Default")
      (node (ref "ETH5") (pin "P$9") (pinfunction "LED1N_P$9") (pintype "bidirectional"))
    )
    (net (code "156") (name "unconnected-(ETH5-LED1P-PadP$10)") (class "Default")
      (node (ref "ETH5") (pin "P$10") (pinfunction "LED1P_P$10") (pintype "bidirectional"))
    )
    (net (code "157") (name "unconnected-(ETH5-LED2N-PadP$11)") (class "Default")
      (node (ref "ETH5") (pin "P$11") (pinfunction "LED2N_P$11") (pintype "bidirectional"))
    )
    (net (code "158") (name "unconnected-(ETH5-LED2P-PadP$12)") (class "Default")
      (node (ref "ETH5") (pin "P$12") (pinfunction "LED2P_P$12") (pintype "bidirectional"))
    )
    (net (code "159") (name "unconnected-(ETH6-7-PadP$7)") (class "Default")
      (node (ref "ETH6") (pin "P$7") (pinfunction "7_P$7") (pintype "bidirectional"))
    )
    (net (code "160") (name "unconnected-(ETH6-8-PadP$8)") (class "Default")
      (node (ref "ETH6") (pin "P$8") (pinfunction "8_P$8") (pintype "bidirectional"))
    )
    (net (code "161") (name "unconnected-(ETH6-LED1N-PadP$9)") (class "Default")
      (node (ref "ETH6") (pin "P$9") (pinfunction "LED1N_P$9") (pintype "bidirectional"))
    )
    (net (code "162") (name "unconnected-(ETH6-LED1P-PadP$10)") (class "Default")
      (node (ref "ETH6") (pin "P$10") (pinfunction "LED1P_P$10") (pintype "bidirectional"))
    )
    (net (code "163") (name "unconnected-(ETH6-LED2N-PadP$11)") (class "Default")
      (node (ref "ETH6") (pin "P$11") (pinfunction "LED2N_P$11") (pintype "bidirectional"))
    )
    (net (code "164") (name "unconnected-(ETH6-LED2P-PadP$12)") (class "Default")
      (node (ref "ETH6") (pin "P$12") (pinfunction "LED2P_P$12") (pintype "bidirectional"))
    )
    (net (code "165") (name "unconnected-(ETH7-3-PadP$3)") (class "Default")
      (node (ref "ETH7") (pin "P$3") (pinfunction "3_P$3") (pintype "bidirectional"))
    )
    (net (code "166") (name "unconnected-(ETH7-4-PadP$4)") (class "Default")
      (node (ref "ETH7") (pin "P$4") (pinfunction "4_P$4") (pintype "bidirectional"))
    )
    (net (code "167") (name "unconnected-(ETH7-7-PadP$7)") (class "Default")
      (node (ref "ETH7") (pin "P$7") (pinfunction "7_P$7") (pintype "bidirectional"))
    )
    (net (code "168") (name "unconnected-(ETH7-LED1N-PadP$9)") (class "Default")
      (node (ref "ETH7") (pin "P$9") (pinfunction "LED1N_P$9") (pintype "bidirectional"))
    )
    (net (code "169") (name "unconnected-(ETH7-LED1P-PadP$10)") (class "Default")
      (node (ref "ETH7") (pin "P$10") (pinfunction "LED1P_P$10") (pintype "bidirectional"))
    )
    (net (code "170") (name "unconnected-(ETH7-LED2N-PadP$11)") (class "Default")
      (node (ref "ETH7") (pin "P$11") (pinfunction "LED2N_P$11") (pintype "bidirectional"))
    )
    (net (code "171") (name "unconnected-(ETH7-LED2P-PadP$12)") (class "Default")
      (node (ref "ETH7") (pin "P$12") (pinfunction "LED2P_P$12") (pintype "bidirectional"))
    )
    (net (code "172") (name "unconnected-(O1-DTR-PadP$1)") (class "Default")
      (node (ref "O1") (pin "P$1") (pinfunction "DTR_P$1") (pintype "bidirectional"))
    )
    (net (code "173") (name "unconnected-(RTC1-32KHZ-PadP$6)") (class "Default")
      (node (ref "RTC1") (pin "P$6") (pinfunction "32KHZ_P$6") (pintype "bidirectional"))
    )
    (net (code "174") (name "unconnected-(RTC1-BAT-PadP$5)") (class "Default")
      (node (ref "RTC1") (pin "P$5") (pinfunction "BAT_P$5") (pintype "bidirectional"))
    )
    (net (code "175") (name "unconnected-(RTC1-RST-PadP$8)") (class "Default")
      (node (ref "RTC1") (pin "P$8") (pinfunction "RST_P$8") (pintype "bidirectional"))
    )
    (net (code "176") (name "unconnected-(RTC1-SQW-PadP$7)") (class "Default")
      (node (ref "RTC1") (pin "P$7") (pinfunction "SQW_P$7") (pintype "bidirectional"))
    )
    (net (code "177") (name "unconnected-(SHT1-ADDR-PadADR)") (class "Default")
      (node (ref "SHT1") (pin "ADR") (pinfunction "ADDR_ADR") (pintype "bidirectional"))
    )
    (net (code "178") (name "unconnected-(SHT1-ALERT-PadALR)") (class "Default")
      (node (ref "SHT1") (pin "ALR") (pinfunction "ALERT_ALR") (pintype "bidirectional"))
    )
    (net (code "179") (name "unconnected-(SHT1-PadRST)") (class "Default")
      (node (ref "SHT1") (pin "RST") (pinfunction "RST_RST") (pintype "bidirectional"))
    )
    (net (code "180") (name "unconnected-(T1-13{slash}SCK{slash}LED-Pad13)") (class "Default")
      (node (ref "T1") (pin "13") (pinfunction "13/SCK/LED_13") (pintype "bidirectional"))
    )
    (net (code "181") (name "unconnected-(T1-23{slash}A9{slash}T{slash}PWM-Pad23{slash}A9)") (class "Default")
      (node (ref "T1") (pin "23/A9") (pinfunction "23/A9/T/PWM_23/A9") (pintype "bidirectional"))
    )
    (net (code "182") (name "unconnected-(T1-A14{slash}DAC-PadRESET{slash}DAC)") (class "Default")
      (node (ref "T1") (pin "RESET/DAC") (pinfunction "A14/DAC_RESET/DAC") (pintype "bidirectional"))
    )
    (net (code "183") (name "unconnected-(T1-PadA10)") (class "Default")
      (node (ref "T1") (pin "A10") (pinfunction "A10_A10") (pintype "bidirectional"))
    )
    (net (code "184") (name "unconnected-(T1-PadPGM)") (class "Default")
      (node (ref "T1") (pin "PGM") (pinfunction "PGM_PGM") (pintype "bidirectional"))
    )
    (net (code "185") (name "unconnected-(U3-ADC6-Pad19)") (class "Default")
      (node (ref "U3") (pin "19") (pinfunction "ADC6_19") (pintype "bidirectional"))
    )
    (net (code "186") (name "unconnected-(U3-ADC7-Pad22)") (class "Default")
      (node (ref "U3") (pin "22") (pinfunction "ADC7_22") (pintype "bidirectional"))
    )
    (net (code "187") (name "unconnected-(U3-PB0(ICP)-Pad12)") (class "Default")
      (node (ref "U3") (pin "12") (pinfunction "PB0(ICP)_12") (pintype "bidirectional"))
    )
    (net (code "188") (name "unconnected-(U3-PB1(OC1A)-Pad13)") (class "Default")
      (node (ref "U3") (pin "13") (pinfunction "PB1(OC1A)_13") (pintype "bidirectional"))
    )
    (net (code "189") (name "unconnected-(U3-PB2(SS{slash}OC1B)-Pad14)") (class "Default")
      (node (ref "U3") (pin "14") (pinfunction "PB2(SS/OC1B)_14") (pintype "bidirectional"))
    )
    (net (code "190") (name "unconnected-(U3-PC0(ADC0)-Pad23)") (class "Default")
      (node (ref "U3") (pin "23") (pinfunction "PC0(ADC0)_23") (pintype "bidirectional"))
    )
    (net (code "191") (name "unconnected-(U3-PC1(ADC1)-Pad24)") (class "Default")
      (node (ref "U3") (pin "24") (pinfunction "PC1(ADC1)_24") (pintype "bidirectional"))
    )
    (net (code "192") (name "unconnected-(U3-PC2(ADC2)-Pad25)") (class "Default")
      (node (ref "U3") (pin "25") (pinfunction "PC2(ADC2)_25") (pintype "bidirectional"))
    )
    (net (code "193") (name "unconnected-(U3-PC3(ADC3)-Pad26)") (class "Default")
      (node (ref "U3") (pin "26") (pinfunction "PC3(ADC3)_26") (pintype "bidirectional"))
    )
    (net (code "194") (name "unconnected-(U3-PD2(INT0)-Pad32)") (class "Default")
      (node (ref "U3") (pin "32") (pinfunction "PD2(INT0)_32") (pintype "bidirectional"))
    )
    (net (code "195") (name "unconnected-(U3-PD4(XCK{slash}T0)-Pad2)") (class "Default")
      (node (ref "U3") (pin "2") (pinfunction "PD4(XCK/T0)_2") (pintype "bidirectional"))
    )
    (net (code "196") (name "unconnected-(U3-PD5(T1)-Pad9)") (class "Default")
      (node (ref "U3") (pin "9") (pinfunction "PD5(T1)_9") (pintype "bidirectional"))
    )
    (net (code "197") (name "unconnected-(U3-PD6(AIN0)-Pad10)") (class "Default")
      (node (ref "U3") (pin "10") (pinfunction "PD6(AIN0)_10") (pintype "bidirectional"))
    )
    (net (code "198") (name "unconnected-(U3-PD7(AIN1)-Pad11)") (class "Default")
      (node (ref "U3") (pin "11") (pinfunction "PD7(AIN1)_11") (pintype "bidirectional"))
    )
    (net (code "199") (name "unconnected-(U4-ADC6-Pad19)") (class "Default")
      (node (ref "U4") (pin "19") (pinfunction "ADC6_19") (pintype "bidirectional"))
    )
    (net (code "200") (name "unconnected-(U4-ADC7-Pad22)") (class "Default")
      (node (ref "U4") (pin "22") (pinfunction "ADC7_22") (pintype "bidirectional"))
    )
    (net (code "201") (name "unconnected-(U4-PB0(ICP)-Pad12)") (class "Default")
      (node (ref "U4") (pin "12") (pinfunction "PB0(ICP)_12") (pintype "bidirectional"))
    )
    (net (code "202") (name "unconnected-(U4-PB1(OC1A)-Pad13)") (class "Default")
      (node (ref "U4") (pin "13") (pinfunction "PB1(OC1A)_13") (pintype "bidirectional"))
    )
    (net (code "203") (name "unconnected-(U4-PB2(SS{slash}OC1B)-Pad14)") (class "Default")
      (node (ref "U4") (pin "14") (pinfunction "PB2(SS/OC1B)_14") (pintype "bidirectional"))
    )
    (net (code "204") (name "unconnected-(U4-PC0(ADC0)-Pad23)") (class "Default")
      (node (ref "U4") (pin "23") (pinfunction "PC0(ADC0)_23") (pintype "bidirectional"))
    )
    (net (code "205") (name "unconnected-(U4-PC1(ADC1)-Pad24)") (class "Default")
      (node (ref "U4") (pin "24") (pinfunction "PC1(ADC1)_24") (pintype "bidirectional"))
    )
    (net (code "206") (name "unconnected-(U4-PC2(ADC2)-Pad25)") (class "Default")
      (node (ref "U4") (pin "25") (pinfunction "PC2(ADC2)_25") (pintype "bidirectional"))
    )
    (net (code "207") (name "unconnected-(U4-PC3(ADC3)-Pad26)") (class "Default")
      (node (ref "U4") (pin "26") (pinfunction "PC3(ADC3)_26") (pintype "bidirectional"))
    )
    (net (code "208") (name "unconnected-(U4-PD2(INT0)-Pad32)") (class "Default")
      (node (ref "U4") (pin "32") (pinfunction "PD2(INT0)_32") (pintype "bidirectional"))
    )
    (net (code "209") (name "unconnected-(U4-PD4(XCK{slash}T0)-Pad2)") (class "Default")
      (node (ref "U4") (pin "2") (pinfunction "PD4(XCK/T0)_2") (pintype "bidirectional"))
    )
    (net (code "210") (name "unconnected-(U4-PD5(T1)-Pad9)") (class "Default")
      (node (ref "U4") (pin "9") (pinfunction "PD5(T1)_9") (pintype "bidirectional"))
    )
    (net (code "211") (name "unconnected-(U4-PD6(AIN0)-Pad10)") (class "Default")
      (node (ref "U4") (pin "10") (pinfunction "PD6(AIN0)_10") (pintype "bidirectional"))
    )
    (net (code "212") (name "unconnected-(U4-PD7(AIN1)-Pad11)") (class "Default")
      (node (ref "U4") (pin "11") (pinfunction "PD7(AIN1)_11") (pintype "bidirectional"))
    )
    (net (code "213") (name "unconnected-(U6-PB0(ICP)-Pad12)") (class "Default")
      (node (ref "U6") (pin "12") (pinfunction "PB0(ICP)_12") (pintype "bidirectional"))
    )
    (net (code "214") (name "unconnected-(U6-PB1(OC1A)-Pad13)") (class "Default")
      (node (ref "U6") (pin "13") (pinfunction "PB1(OC1A)_13") (pintype "bidirectional"))
    )
    (net (code "215") (name "unconnected-(U6-PB2(SS{slash}OC1B)-Pad14)") (class "Default")
      (node (ref "U6") (pin "14") (pinfunction "PB2(SS/OC1B)_14") (pintype "bidirectional"))
    )
    (net (code "216") (name "unconnected-(U6-PB6(XTAL1{slash}TOSC1)-Pad7)") (class "Default")
      (node (ref "U6") (pin "7") (pinfunction "PB6(XTAL1/TOSC1)_7") (pintype "bidirectional"))
    )
    (net (code "217") (name "unconnected-(U6-PB7(XTAL2{slash}TOSC2)-Pad8)") (class "Default")
      (node (ref "U6") (pin "8") (pinfunction "PB7(XTAL2/TOSC2)_8") (pintype "bidirectional"))
    )
    (net (code "218") (name "unconnected-(U6-PD6(AIN0)-Pad10)") (class "Default")
      (node (ref "U6") (pin "10") (pinfunction "PD6(AIN0)_10") (pintype "bidirectional"))
    )
    (net (code "219") (name "unconnected-(U6-PD7(AIN1)-Pad11)") (class "Default")
      (node (ref "U6") (pin "11") (pinfunction "PD7(AIN1)_11") (pintype "bidirectional"))
    )
  )
)
